# EasyEDA_proj.net
KiCad netlist of a schematic drawn in EasyEDA Pro
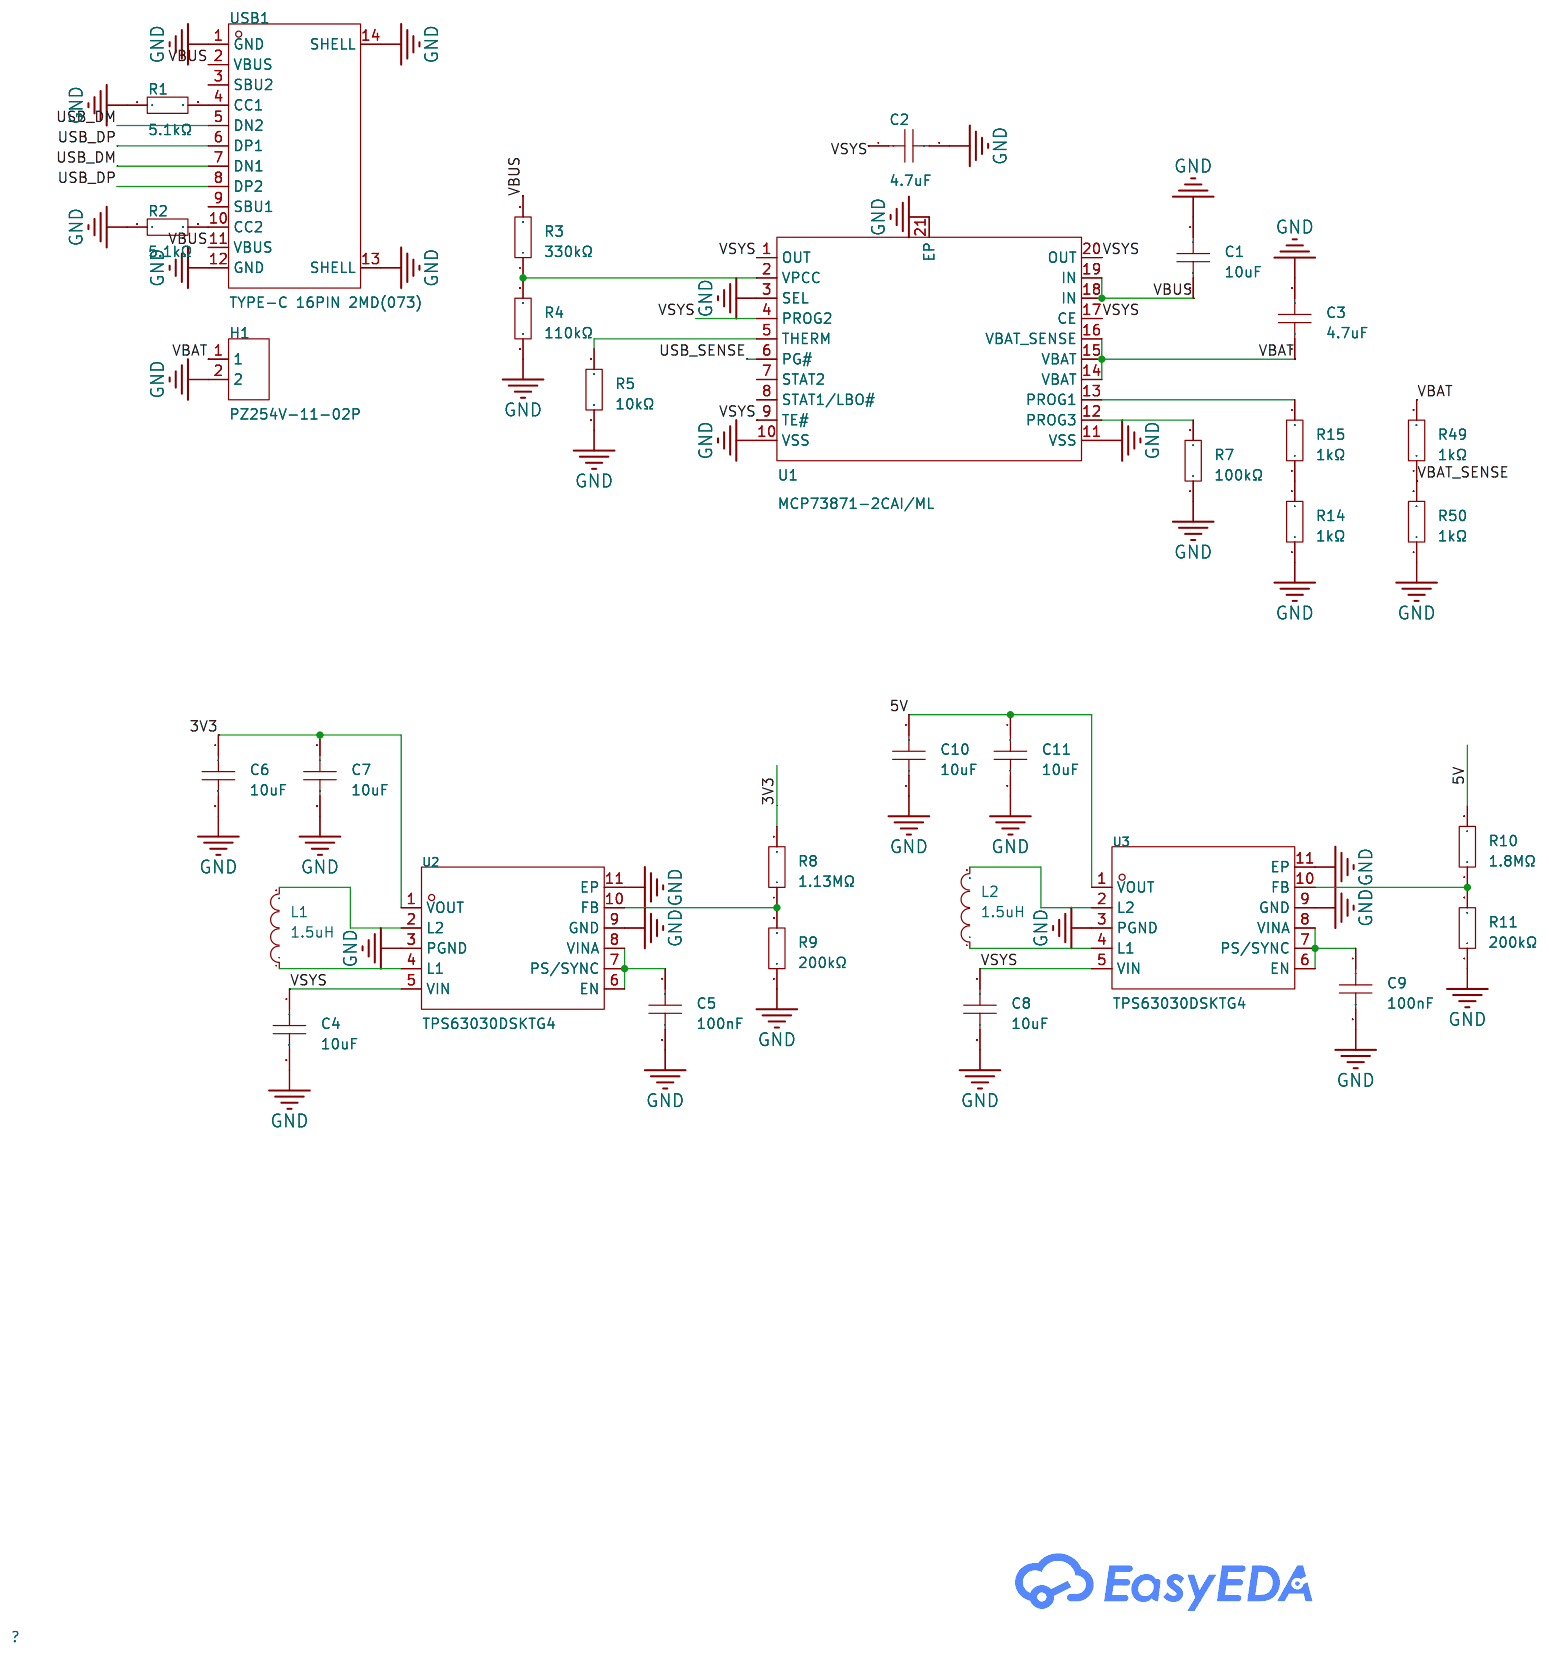
[diagram p0: Power]
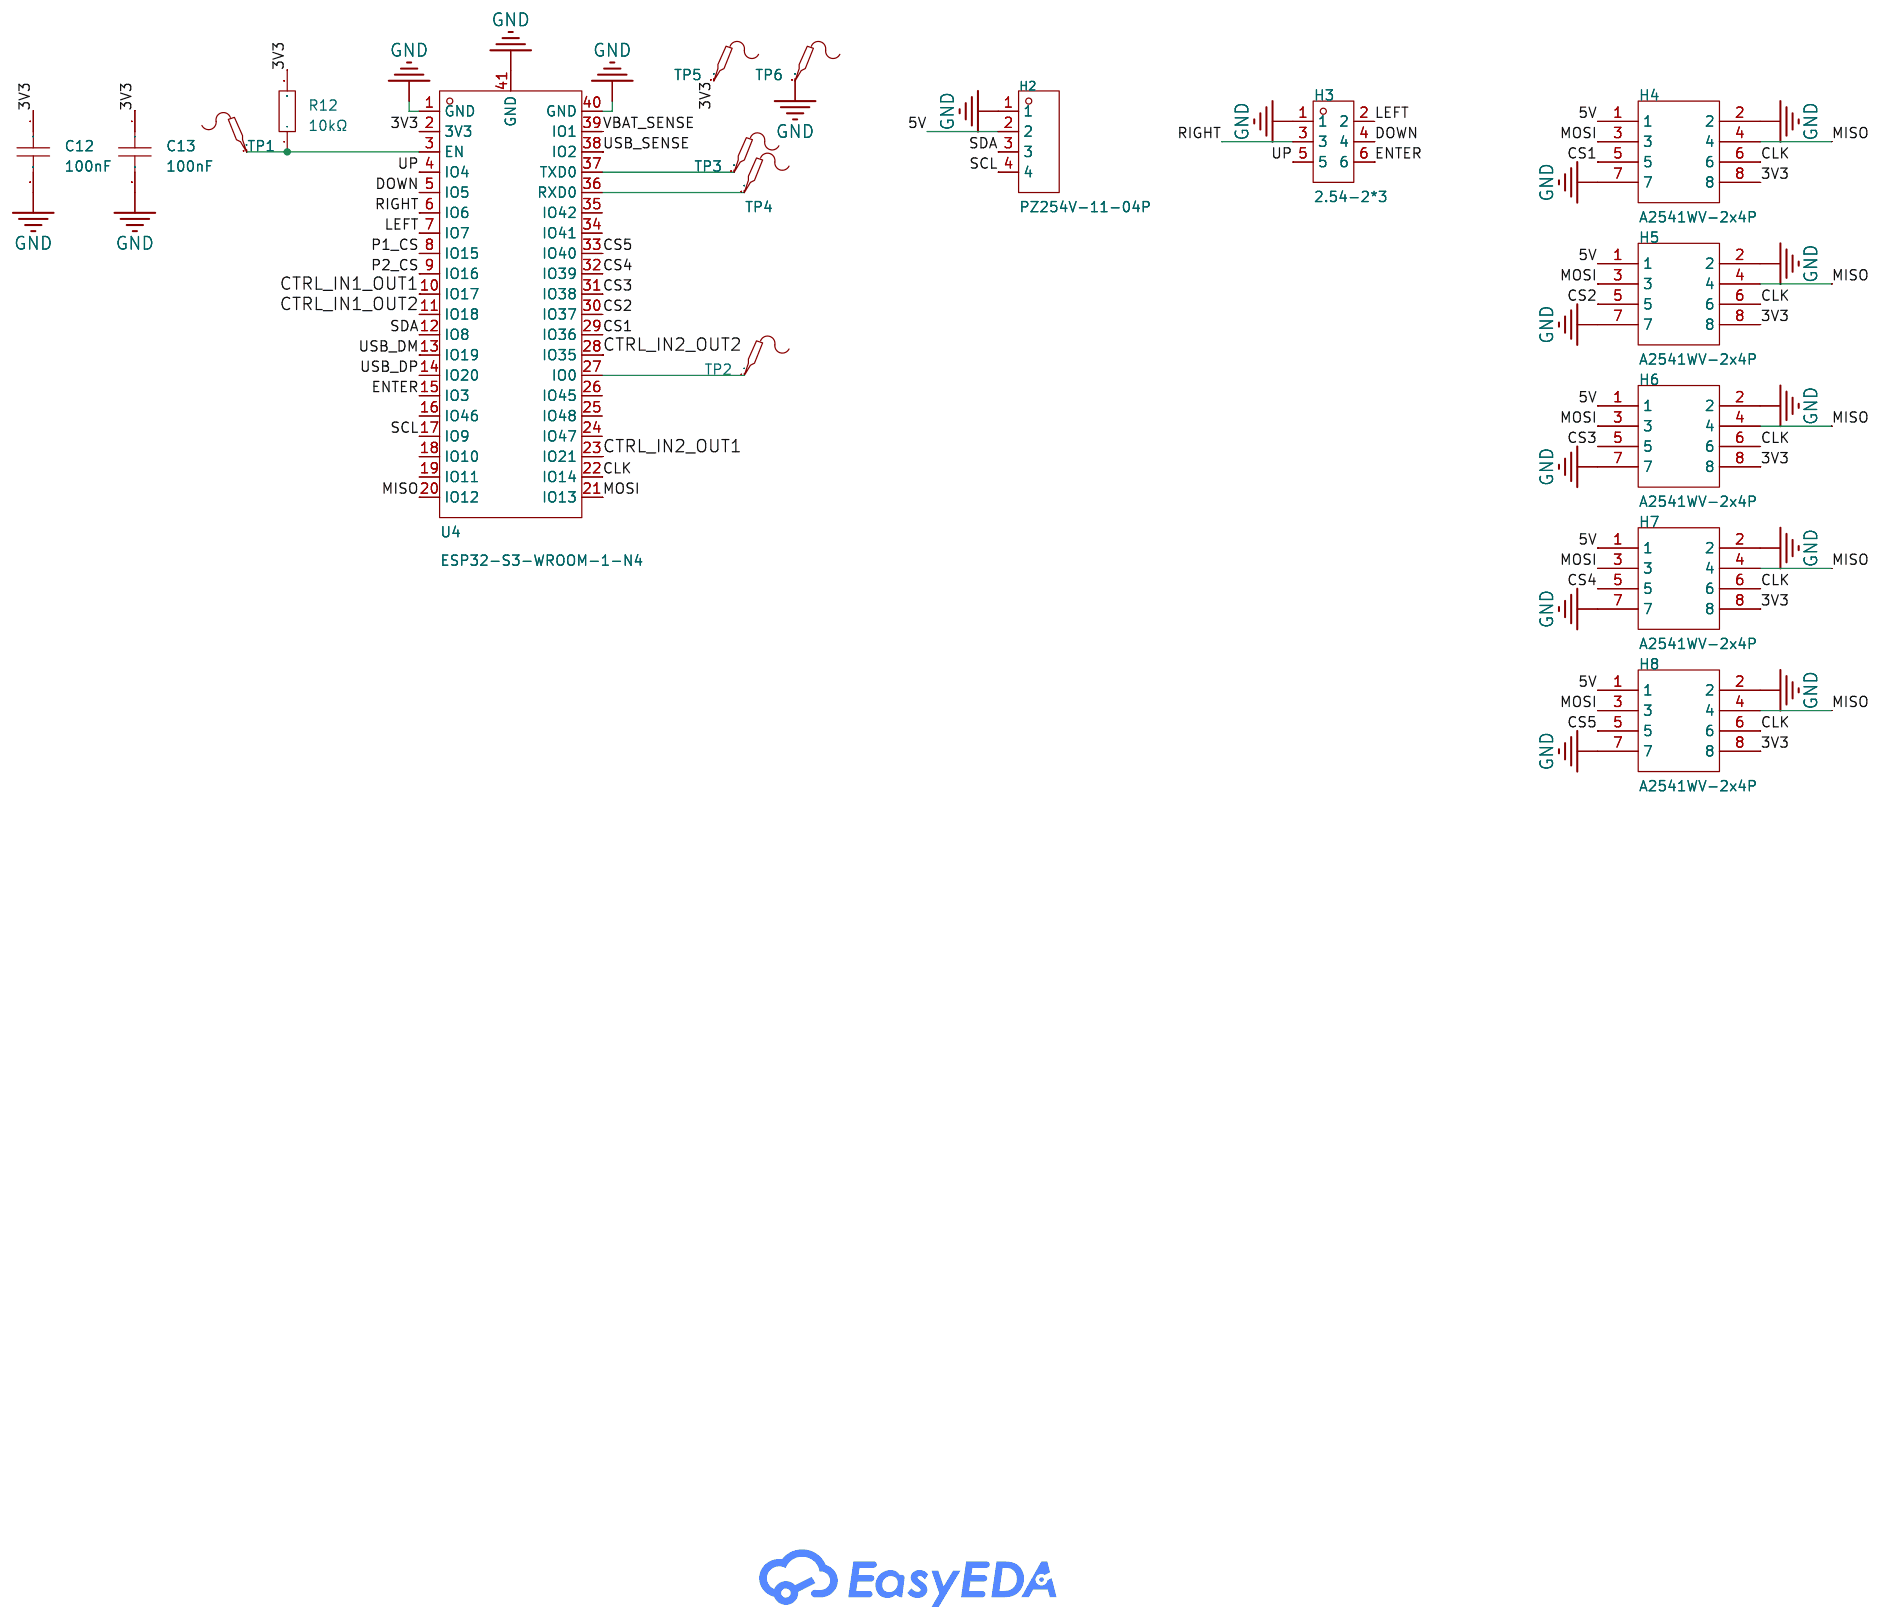
[diagram p1: MCU]
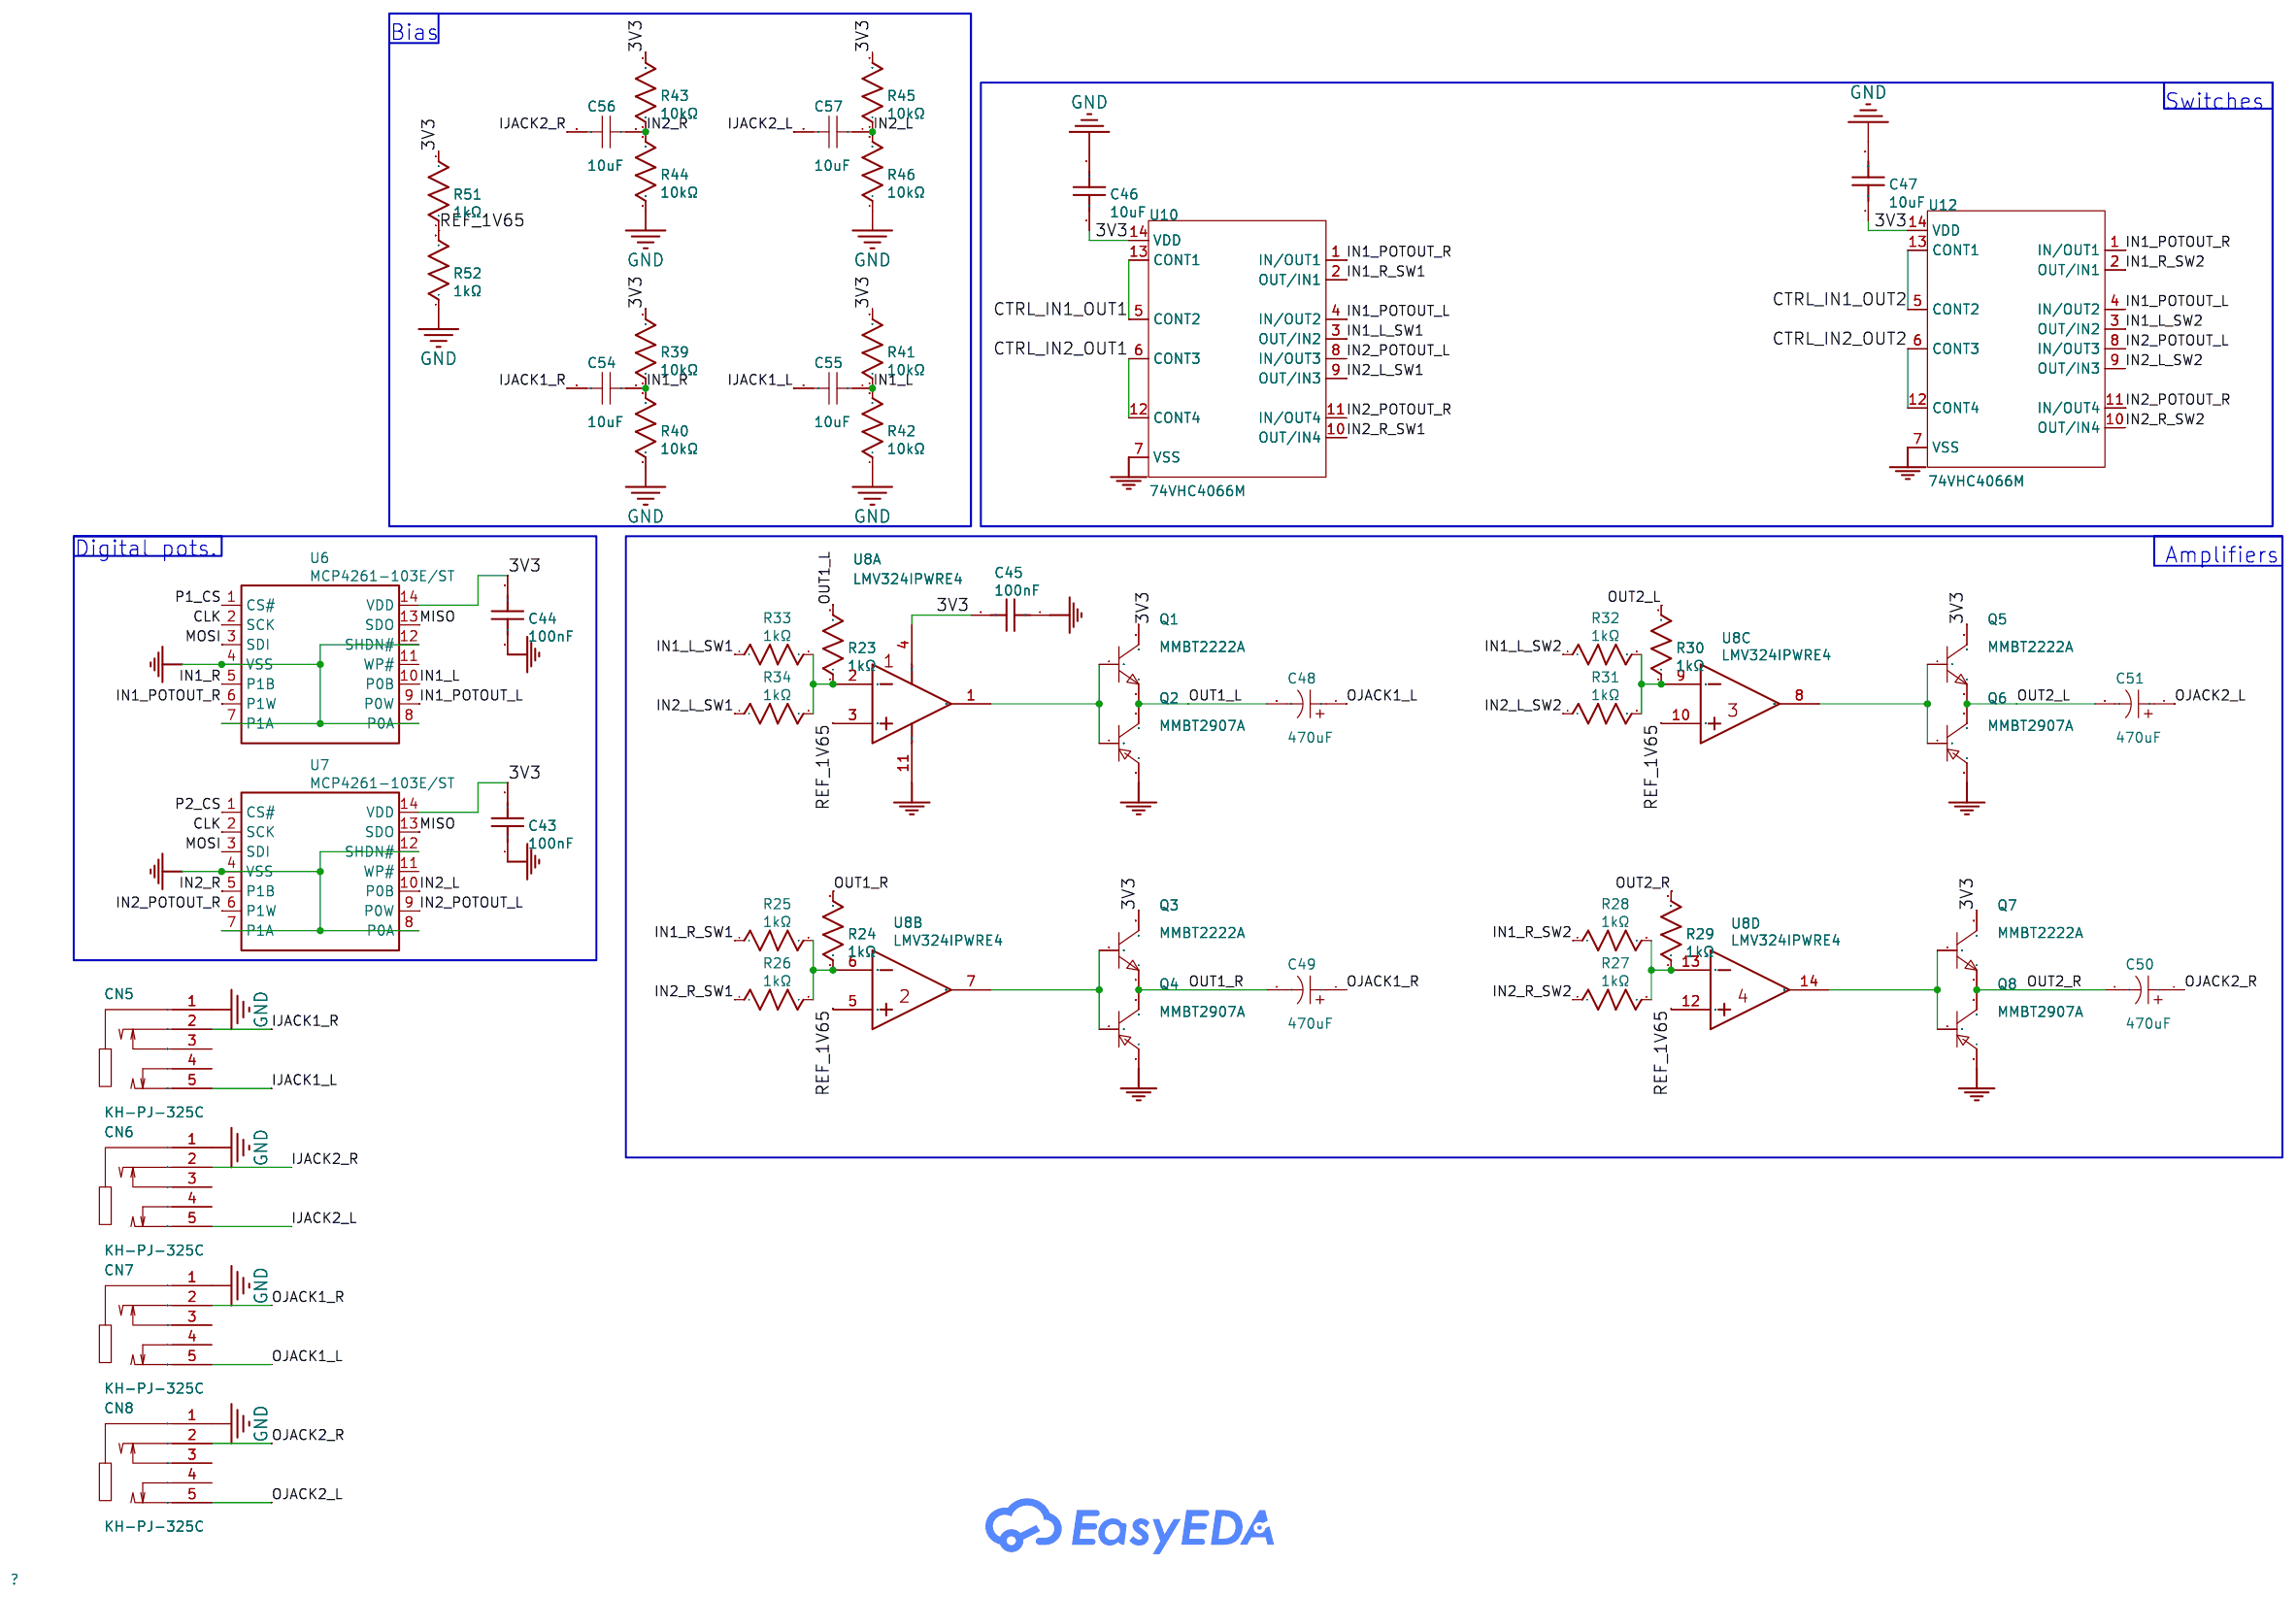
[diagram p2: Audio]

(export (version "E")
  (design (tool "Eeschema 10.0.6"))
  (components
    (comp (ref "C1")
      (value "10uF")
      (footprint "easyedapro:C0603")
      (description "Capacitance:10uF Tolerance:±20% Tolerance:±20% Voltage Rating:6.3V Temperature Coefficient:X5R")
      (fields (field (name "Manufacturer Part") "C0603B106M007T") (field (name "Manufacturer") "IHHEC(禾伸堂)"))
      (libsource (lib "easyedapro") (part "CAP"))
    )
    (comp (ref "C2")
      (value "4.7uF")
      (footprint "easyedapro:C0603")
      (description "Capacitance:4.7uF Tolerance:±10% Tolerance:±10% Voltage Rating:10V Temperature Coefficient:X5R")
      (fields
        (field (name "Manufacturer Part") "CL10A475KP8NNNC")
        (field (name "Manufacturer") "SAMSUNG(三星)")
      )
      (libsource (lib "easyedapro") (part "CAP"))
    )
    (comp (ref "C3")
      (value "4.7uF")
      (footprint "easyedapro:C0603")
      (description "Capacitance:4.7uF Tolerance:±10% Tolerance:±10% Voltage Rating:10V Temperature Coefficient:X5R")
      (fields
        (field (name "Manufacturer Part") "CL10A475KP8NNNC")
        (field (name "Manufacturer") "SAMSUNG(三星)")
      )
      (libsource (lib "easyedapro") (part "CAP"))
    )
    (comp (ref "C4")
      (value "10uF")
      (footprint "easyedapro:C0603")
      (description "Capacitance:10uF Tolerance:±20% Tolerance:±20% Voltage Rating:6.3V Temperature Coefficient:X5R")
      (fields (field (name "Manufacturer Part") "C0603B106M007T") (field (name "Manufacturer") "IHHEC(禾伸堂)"))
      (libsource (lib "easyedapro") (part "CAP"))
    )
    (comp (ref "C5")
      (value "100nF")
      (footprint "easyedapro:C0603")
      (description "Capacitance:100nF Tolerance:±10% Tolerance:±10% Voltage Rating:50V Temperature Coefficient:X7R")
      (fields
        (field (name "Manufacturer Part") "CC0603KRX7R9BB104")
        (field (name "Manufacturer") "YAGEO(国巨)")
      )
      (libsource (lib "easyedapro") (part "CAP"))
    )
    (comp (ref "C6")
      (value "10uF")
      (footprint "easyedapro:C0603")
      (description "Capacitance:10uF Tolerance:±20% Tolerance:±20% Voltage Rating:6.3V Temperature Coefficient:X5R")
      (fields (field (name "Manufacturer Part") "C0603B106M007T") (field (name "Manufacturer") "IHHEC(禾伸堂)"))
      (libsource (lib "easyedapro") (part "CAP"))
    )
    (comp (ref "C7")
      (value "10uF")
      (footprint "easyedapro:C0603")
      (description "Capacitance:10uF Tolerance:±20% Tolerance:±20% Voltage Rating:6.3V Temperature Coefficient:X5R")
      (fields (field (name "Manufacturer Part") "C0603B106M007T") (field (name "Manufacturer") "IHHEC(禾伸堂)"))
      (libsource (lib "easyedapro") (part "CAP"))
    )
    (comp (ref "C8")
      (value "10uF")
      (footprint "easyedapro:C0603")
      (description "Capacitance:10uF Tolerance:±20% Tolerance:±20% Voltage Rating:6.3V Temperature Coefficient:X5R")
      (fields (field (name "Manufacturer Part") "C0603B106M007T") (field (name "Manufacturer") "IHHEC(禾伸堂)"))
      (libsource (lib "easyedapro") (part "CAP"))
    )
    (comp (ref "C9")
      (value "100nF")
      (footprint "easyedapro:C0603")
      (description "Capacitance:100nF Tolerance:±10% Tolerance:±10% Voltage Rating:50V Temperature Coefficient:X7R")
      (fields
        (field (name "Manufacturer Part") "CC0603KRX7R9BB104")
        (field (name "Manufacturer") "YAGEO(国巨)")
      )
      (libsource (lib "easyedapro") (part "CAP"))
    )
    (comp (ref "C10")
      (value "10uF")
      (footprint "easyedapro:C0603")
      (description "Capacitance:10uF Tolerance:±20% Tolerance:±20% Voltage Rating:6.3V Temperature Coefficient:X5R")
      (fields (field (name "Manufacturer Part") "C0603B106M007T") (field (name "Manufacturer") "IHHEC(禾伸堂)"))
      (libsource (lib "easyedapro") (part "CAP"))
    )
    (comp (ref "C11")
      (value "10uF")
      (footprint "easyedapro:C0603")
      (description "Capacitance:10uF Tolerance:±20% Tolerance:±20% Voltage Rating:6.3V Temperature Coefficient:X5R")
      (fields (field (name "Manufacturer Part") "C0603B106M007T") (field (name "Manufacturer") "IHHEC(禾伸堂)"))
      (libsource (lib "easyedapro") (part "CAP"))
    )
    (comp (ref "H1")
      (value "PZ254V-11-02P")
      (footprint "easyedapro:HDR-TH_2P-P2.54-V-M")
      (fields (field (name "Manufacturer") "XFCN(兴飞)"))
      (libsource (lib "easyedapro") (part "PZ254V-11-02P"))
    )
    (comp (ref "L1")
      (value "1.5uH")
      (footprint "easyedapro:L0603")
      (fields
        (field (name "Manufacturer Part") "LB3218T1R5M")
        (field (name "Manufacturer") "TAIYO YUDEN(太诱)")
      )
      (libsource (lib "easyedapro") (part "电感"))
    )
    (comp (ref "L2")
      (value "1.5uH")
      (footprint "easyedapro:L0603")
      (fields
        (field (name "Manufacturer Part") "LB3218T1R5M")
        (field (name "Manufacturer") "TAIYO YUDEN(太诱)")
      )
      (libsource (lib "easyedapro") (part "电感"))
    )
    (comp (ref "R1")
      (value "5.1kΩ")
      (footprint "easyedapro:R0603")
      (fields
        (field (name "Manufacturer Part") "HoAR0603-1/10W-5.1KR-0.1%-TCR25")
        (field (name "Manufacturer") "Milliohm(毫欧)")
      )
      (libsource (lib "easyedapro") (part "Res"))
    )
    (comp (ref "R2")
      (value "5.1kΩ")
      (footprint "easyedapro:R0603")
      (fields
        (field (name "Manufacturer Part") "HoAR0603-1/10W-5.1KR-0.1%-TCR25")
        (field (name "Manufacturer") "Milliohm(毫欧)")
      )
      (libsource (lib "easyedapro") (part "Res"))
    )
    (comp (ref "R3")
      (value "330kΩ")
      (footprint "easyedapro:R0603")
      (fields (field (name "Manufacturer Part") "HPCR0603F330KK9") (field (name "Manufacturer") "RESI(开步睿思)"))
      (libsource (lib "easyedapro") (part "Res"))
    )
    (comp (ref "R4")
      (value "110kΩ")
      (footprint "easyedapro:R0603")
      (fields (field (name "Manufacturer Part") "PTFR0603B110KN9") (field (name "Manufacturer") "RESI(开步睿思)"))
      (libsource (lib "easyedapro") (part "Res"))
    )
    (comp (ref "R5")
      (value "10kΩ")
      (footprint "easyedapro:R0603")
      (fields (field (name "Manufacturer Part") "SCR0603J10K") (field (name "Manufacturer") "VO(翔胜)"))
      (libsource (lib "easyedapro") (part "Res"))
    )
    (comp (ref "R7")
      (value "100kΩ")
      (footprint "easyedapro:R0603")
      (fields (field (name "Manufacturer Part") "SCR0603F100K") (field (name "Manufacturer") "VO(翔胜)"))
      (libsource (lib "easyedapro") (part "Res"))
    )
    (comp (ref "R8")
      (value "1.13MΩ")
      (footprint "easyedapro:R0603")
      (fields (field (name "Manufacturer Part") "RTT031134FTP") (field (name "Manufacturer") "RALEC(旺诠)"))
      (libsource (lib "easyedapro") (part "Res"))
    )
    (comp (ref "R9")
      (value "200kΩ")
      (footprint "easyedapro:R0603")
      (fields (field (name "Manufacturer Part") "SCR0603F200K") (field (name "Manufacturer") "VO(翔胜)"))
      (libsource (lib "easyedapro") (part "Res"))
    )
    (comp (ref "R10")
      (value "1.8MΩ")
      (footprint "easyedapro:R0603")
      (fields (field (name "Manufacturer Part") "FRC0603J185TS") (field (name "Manufacturer") "FOJAN(富捷)"))
      (libsource (lib "easyedapro") (part "Res"))
    )
    (comp (ref "R11")
      (value "200kΩ")
      (footprint "easyedapro:R0603")
      (fields (field (name "Manufacturer Part") "SCR0603F200K") (field (name "Manufacturer") "VO(翔胜)"))
      (libsource (lib "easyedapro") (part "Res"))
    )
    (comp (ref "R14")
      (value "1kΩ")
      (footprint "easyedapro:R0603")
      (fields
        (field (name "Manufacturer Part") "0603WAF1001T5E")
        (field (name "Manufacturer") "UNI-ROYAL(厚声)")
      )
      (libsource (lib "easyedapro") (part "Res"))
    )
    (comp (ref "R15")
      (value "1kΩ")
      (footprint "easyedapro:R0603")
      (fields
        (field (name "Manufacturer Part") "0603WAF1001T5E")
        (field (name "Manufacturer") "UNI-ROYAL(厚声)")
      )
      (libsource (lib "easyedapro") (part "Res"))
    )
    (comp (ref "R49")
      (value "1kΩ")
      (footprint "easyedapro:R0603")
      (fields
        (field (name "Manufacturer Part") "0603WAF1001T5E")
        (field (name "Manufacturer") "UNI-ROYAL(厚声)")
      )
      (libsource (lib "easyedapro") (part "Res"))
    )
    (comp (ref "R50")
      (value "1kΩ")
      (footprint "easyedapro:R0603")
      (fields
        (field (name "Manufacturer Part") "0603WAF1001T5E")
        (field (name "Manufacturer") "UNI-ROYAL(厚声)")
      )
      (libsource (lib "easyedapro") (part "Res"))
    )
    (comp (ref "U1")
      (value "MCP73871-2CAI/ML")
      (footprint "easyedapro:QFN-20_L4.0-W4.0-P0.50-BL-EP2.7")
      (fields (field (name "Manufacturer") "MICROCHIP(美国微芯)"))
      (libsource (lib "easyedapro") (part "MCP73871-2CAI/ML"))
    )
    (comp (ref "U2")
      (value "TPS63030DSKTG4")
      (footprint "easyedapro:SON-10_L2.5-W2.5-P0.50-TL-EP")
      (fields (field (name "Manufacturer") "TI(德州仪器)"))
      (libsource (lib "easyedapro") (part "TPS63030DSKTG4"))
    )
    (comp (ref "U3")
      (value "TPS63030DSKTG4")
      (footprint "easyedapro:SON-10_L2.5-W2.5-P0.50-TL-EP")
      (fields (field (name "Manufacturer") "TI(德州仪器)"))
      (libsource (lib "easyedapro") (part "TPS63030DSKTG4"))
    )
    (comp (ref "USB1")
      (value "TYPE-C 16PIN 2MD(073)")
      (footprint "easyedapro:USB-C-SMD_TYPE-C-6PIN-2MD-073")
      (fields (field (name "Manufacturer") "SHOU HAN(首韩)"))
      (libsource (lib "easyedapro") (part "TYPE-C 16PIN 2MD(073)"))
    )
    (comp (ref "C12")
      (value "100nF")
      (footprint "easyedapro:C0603")
      (description "Capacitance:100nF Tolerance:±10% Tolerance:±10% Voltage Rating:50V Temperature Coefficient:X7R")
      (fields
        (field (name "Manufacturer Part") "CC0603KRX7R9BB104")
        (field (name "Manufacturer") "YAGEO(国巨)")
      )
      (libsource (lib "easyedapro") (part "CAP"))
    )
    (comp (ref "C13")
      (value "100nF")
      (footprint "easyedapro:C0603")
      (description "Capacitance:100nF Tolerance:±10% Tolerance:±10% Voltage Rating:50V Temperature Coefficient:X7R")
      (fields
        (field (name "Manufacturer Part") "CC0603KRX7R9BB104")
        (field (name "Manufacturer") "YAGEO(国巨)")
      )
      (libsource (lib "easyedapro") (part "CAP"))
    )
    (comp (ref "H2")
      (value "PZ254V-11-04P")
      (footprint "easyedapro:HDR-TH_4P-P2.54-V-M")
      (fields (field (name "Manufacturer") "XFCN(兴飞)"))
      (libsource (lib "easyedapro") (part "PZ254V-11-04P_C2691448"))
    )
    (comp (ref "H3")
      (value "2.54-2*3")
      (footprint "easyedapro:HDR-TH_6P-P2.54-V-R2-C3-S2.54_A2541WV-2X3P")
      (fields (field (name "Manufacturer") "ZHOURI(洲日)"))
      (libsource (lib "easyedapro") (part "2.54-2*3"))
    )
    (comp (ref "H4")
      (value "A2541WV-2x4P")
      (footprint "easyedapro:HDR-TH_8P-P2.54-V-R2-C4-S2.54_A2541WV-2X4P")
      (fields (field (name "Manufacturer") "CJT(长江连接器)"))
      (libsource (lib "easyedapro") (part "A2541WV-2X4P"))
    )
    (comp (ref "H5")
      (value "A2541WV-2x4P")
      (footprint "easyedapro:HDR-TH_8P-P2.54-V-R2-C4-S2.54_A2541WV-2X4P")
      (fields (field (name "Manufacturer") "CJT(长江连接器)"))
      (libsource (lib "easyedapro") (part "A2541WV-2X4P"))
    )
    (comp (ref "H6")
      (value "A2541WV-2x4P")
      (footprint "easyedapro:HDR-TH_8P-P2.54-V-R2-C4-S2.54_A2541WV-2X4P")
      (fields (field (name "Manufacturer") "CJT(长江连接器)"))
      (libsource (lib "easyedapro") (part "A2541WV-2X4P"))
    )
    (comp (ref "H7")
      (value "A2541WV-2x4P")
      (footprint "easyedapro:HDR-TH_8P-P2.54-V-R2-C4-S2.54_A2541WV-2X4P")
      (fields (field (name "Manufacturer") "CJT(长江连接器)"))
      (libsource (lib "easyedapro") (part "A2541WV-2X4P"))
    )
    (comp (ref "H8")
      (value "A2541WV-2x4P")
      (footprint "easyedapro:HDR-TH_8P-P2.54-V-R2-C4-S2.54_A2541WV-2X4P")
      (fields (field (name "Manufacturer") "CJT(长江连接器)"))
      (libsource (lib "easyedapro") (part "A2541WV-2X4P"))
    )
    (comp (ref "R12")
      (value "10kΩ")
      (footprint "easyedapro:R0603")
      (fields (field (name "Manufacturer Part") "SCR0603J10K") (field (name "Manufacturer") "VO(翔胜)"))
      (libsource (lib "easyedapro") (part "Res"))
    )
    (comp (ref "TP1")
      (value "~")
      (footprint "easyedapro:Test-Point-0.5mm")
      (description "Test Point 测试点")
      (libsource (lib "easyedapro") (part "Test-Point"))
    )
    (comp (ref "TP2")
      (value "~")
      (footprint "easyedapro:Test-Point-0.5mm")
      (description "Test Point 测试点")
      (libsource (lib "easyedapro") (part "Test-Point"))
    )
    (comp (ref "TP3")
      (value "~")
      (footprint "easyedapro:Test-Point-0.5mm")
      (description "Test Point 测试点")
      (libsource (lib "easyedapro") (part "Test-Point"))
    )
    (comp (ref "TP4")
      (value "~")
      (footprint "easyedapro:Test-Point-0.5mm")
      (description "Test Point 测试点")
      (libsource (lib "easyedapro") (part "Test-Point"))
    )
    (comp (ref "TP5")
      (value "~")
      (footprint "easyedapro:Test-Point-0.5mm")
      (description "Test Point 测试点")
      (libsource (lib "easyedapro") (part "Test-Point"))
    )
    (comp (ref "TP6")
      (value "~")
      (footprint "easyedapro:Test-Point-0.5mm")
      (description "Test Point 测试点")
      (libsource (lib "easyedapro") (part "Test-Point"))
    )
    (comp (ref "U4")
      (value "ESP32-S3-WROOM-1-N4")
      (footprint "easyedapro:WIFIM-SMD_ESP32-S3-WROOM-1-N8")
      (fields (field (name "Manufacturer") "ESPRESSIF(乐鑫)"))
      (libsource (lib "easyedapro") (part "ESP32-S3-WROOM-1-N4"))
    )
    (comp (ref "C43")
      (value "100nF")
      (footprint "easyedapro:C0603")
      (description "Capacitance:100nF Tolerance:±10% Tolerance:±10% Voltage Rating:50V Temperature Coefficient:X7R")
      (fields (field (name "Manufacturer") "YAGEO(国巨)"))
      (libsource (lib "easyedapro") (part "0.1u"))
    )
    (comp (ref "C44")
      (value "100nF")
      (footprint "easyedapro:C0603")
      (description "Capacitance:100nF Tolerance:±10% Tolerance:±10% Voltage Rating:50V Temperature Coefficient:X7R")
      (fields (field (name "Manufacturer") "YAGEO(国巨)"))
      (libsource (lib "easyedapro") (part "0.1u"))
    )
    (comp (ref "C45")
      (value "100nF")
      (footprint "easyedapro:C0603")
      (description "Capacitance:100nF Tolerance:±10% Tolerance:±10% Voltage Rating:50V Temperature Coefficient:X7R")
      (fields (field (name "Manufacturer") "YAGEO(国巨)"))
      (libsource (lib "easyedapro") (part "0.1u"))
    )
    (comp (ref "C46")
      (value "10uF")
      (footprint "easyedapro:C0603")
      (description "Capacitance:10uF Tolerance:±20% Tolerance:±20% Voltage Rating:6.3V Temperature Coefficient:X5R")
      (fields (field (name "Manufacturer") "IHHEC(禾伸堂)"))
      (libsource (lib "easyedapro") (part "10uF"))
    )
    (comp (ref "C47")
      (value "10uF")
      (footprint "easyedapro:C0603")
      (description "Capacitance:10uF Tolerance:±20% Tolerance:±20% Voltage Rating:6.3V Temperature Coefficient:X5R")
      (fields (field (name "Manufacturer") "IHHEC(禾伸堂)"))
      (libsource (lib "easyedapro") (part "10uF"))
    )
    (comp (ref "C48")
      (value "470uF")
      (footprint "easyedapro:CAP-SMD_L7.3-W4.3-FD")
      (fields
        (field (name "Manufacturer Part") "CA45-D-6.3V-470UF-K")
        (field (name "Manufacturer") "CEC(振华新云)")
      )
      (libsource (lib "easyedapro") (part "CA45-D-6.3V-470UF-K"))
    )
    (comp (ref "C49")
      (value "470uF")
      (footprint "easyedapro:CAP-SMD_L7.3-W4.3-FD")
      (fields
        (field (name "Manufacturer Part") "CA45-D-6.3V-470UF-K")
        (field (name "Manufacturer") "CEC(振华新云)")
      )
      (libsource (lib "easyedapro") (part "CA45-D-6.3V-470UF-K"))
    )
    (comp (ref "C50")
      (value "470uF")
      (footprint "easyedapro:CAP-SMD_L7.3-W4.3-FD")
      (fields
        (field (name "Manufacturer Part") "CA45-D-6.3V-470UF-K")
        (field (name "Manufacturer") "CEC(振华新云)")
      )
      (libsource (lib "easyedapro") (part "CA45-D-6.3V-470UF-K"))
    )
    (comp (ref "C51")
      (value "470uF")
      (footprint "easyedapro:CAP-SMD_L7.3-W4.3-FD")
      (fields
        (field (name "Manufacturer Part") "CA45-D-6.3V-470UF-K")
        (field (name "Manufacturer") "CEC(振华新云)")
      )
      (libsource (lib "easyedapro") (part "CA45-D-6.3V-470UF-K"))
    )
    (comp (ref "C54")
      (value "10uF")
      (footprint "easyedapro:C0603")
      (description "Capacitance:10uF Tolerance:±20% Tolerance:±20% Voltage Rating:6.3V Temperature Coefficient:X5R")
      (fields (field (name "Manufacturer Part") "C0603B106M007T") (field (name "Manufacturer") "IHHEC(禾伸堂)"))
      (libsource (lib "easyedapro") (part "CAP"))
    )
    (comp (ref "C55")
      (value "10uF")
      (footprint "easyedapro:C0603")
      (description "Capacitance:10uF Tolerance:±20% Tolerance:±20% Voltage Rating:6.3V Temperature Coefficient:X5R")
      (fields (field (name "Manufacturer Part") "C0603B106M007T") (field (name "Manufacturer") "IHHEC(禾伸堂)"))
      (libsource (lib "easyedapro") (part "CAP"))
    )
    (comp (ref "C56")
      (value "10uF")
      (footprint "easyedapro:C0603")
      (description "Capacitance:10uF Tolerance:±20% Tolerance:±20% Voltage Rating:6.3V Temperature Coefficient:X5R")
      (fields (field (name "Manufacturer Part") "C0603B106M007T") (field (name "Manufacturer") "IHHEC(禾伸堂)"))
      (libsource (lib "easyedapro") (part "CAP"))
    )
    (comp (ref "C57")
      (value "10uF")
      (footprint "easyedapro:C0603")
      (description "Capacitance:10uF Tolerance:±20% Tolerance:±20% Voltage Rating:6.3V Temperature Coefficient:X5R")
      (fields (field (name "Manufacturer Part") "C0603B106M007T") (field (name "Manufacturer") "IHHEC(禾伸堂)"))
      (libsource (lib "easyedapro") (part "CAP"))
    )
    (comp (ref "CN5")
      (value "KH-PJ-325C")
      (footprint "easyedapro:AUDIO-TH_KH-PJ-325C")
      (description "Connector Type:3.5mm Headphone Jack Contact Material:Brass；Bronze Contact Plating:Gold；Tin")
      (fields (field (name "Manufacturer") "kinghelm(金航标)"))
      (libsource (lib "easyedapro") (part "KH-PJ-325C"))
    )
    (comp (ref "CN6")
      (value "KH-PJ-325C")
      (footprint "easyedapro:AUDIO-TH_KH-PJ-325C")
      (description "Connector Type:3.5mm Headphone Jack Contact Material:Brass；Bronze Contact Plating:Gold；Tin")
      (fields (field (name "Manufacturer") "kinghelm(金航标)"))
      (libsource (lib "easyedapro") (part "KH-PJ-325C"))
    )
    (comp (ref "CN7")
      (value "KH-PJ-325C")
      (footprint "easyedapro:AUDIO-TH_KH-PJ-325C")
      (description "Connector Type:3.5mm Headphone Jack Contact Material:Brass；Bronze Contact Plating:Gold；Tin")
      (fields (field (name "Manufacturer") "kinghelm(金航标)"))
      (libsource (lib "easyedapro") (part "KH-PJ-325C"))
    )
    (comp (ref "CN8")
      (value "KH-PJ-325C")
      (footprint "easyedapro:AUDIO-TH_KH-PJ-325C")
      (description "Connector Type:3.5mm Headphone Jack Contact Material:Brass；Bronze Contact Plating:Gold；Tin")
      (fields (field (name "Manufacturer") "kinghelm(金航标)"))
      (libsource (lib "easyedapro") (part "KH-PJ-325C"))
    )
    (comp (ref "Q1")
      (value "MMBT2222A")
      (footprint "easyedapro:SOT-23-3_L2.9-W1.6-P1.90-LS2.8-BR")
      (fields (field (name "Manufacturer") "TDSEMIC(拓电半导体)"))
      (libsource (lib "easyedapro") (part "MMBT2222A_C42441802"))
    )
    (comp (ref "Q2")
      (value "MMBT2907A")
      (footprint "easyedapro:SOT-23-3_L2.9-W1.3-P1.90-LS2.4-BR")
      (fields (field (name "Manufacturer") "R+O(宏嘉诚)"))
      (libsource (lib "easyedapro") (part "MMBT2907A_C7420352"))
    )
    (comp (ref "Q3")
      (value "MMBT2222A")
      (footprint "easyedapro:SOT-23-3_L2.9-W1.6-P1.90-LS2.8-BR")
      (fields (field (name "Manufacturer") "TDSEMIC(拓电半导体)"))
      (libsource (lib "easyedapro") (part "MMBT2222A_C42441802"))
    )
    (comp (ref "Q4")
      (value "MMBT2907A")
      (footprint "easyedapro:SOT-23-3_L2.9-W1.3-P1.90-LS2.4-BR")
      (fields (field (name "Manufacturer") "R+O(宏嘉诚)"))
      (libsource (lib "easyedapro") (part "MMBT2907A_C7420352"))
    )
    (comp (ref "Q5")
      (value "MMBT2222A")
      (footprint "easyedapro:SOT-23-3_L2.9-W1.6-P1.90-LS2.8-BR")
      (fields (field (name "Manufacturer") "TDSEMIC(拓电半导体)"))
      (libsource (lib "easyedapro") (part "MMBT2222A_C42441802"))
    )
    (comp (ref "Q6")
      (value "MMBT2907A")
      (footprint "easyedapro:SOT-23-3_L2.9-W1.3-P1.90-LS2.4-BR")
      (fields (field (name "Manufacturer") "R+O(宏嘉诚)"))
      (libsource (lib "easyedapro") (part "MMBT2907A_C7420352"))
    )
    (comp (ref "Q7")
      (value "MMBT2222A")
      (footprint "easyedapro:SOT-23-3_L2.9-W1.6-P1.90-LS2.8-BR")
      (fields (field (name "Manufacturer") "TDSEMIC(拓电半导体)"))
      (libsource (lib "easyedapro") (part "MMBT2222A_C42441802"))
    )
    (comp (ref "Q8")
      (value "MMBT2907A")
      (footprint "easyedapro:SOT-23-3_L2.9-W1.3-P1.90-LS2.4-BR")
      (fields (field (name "Manufacturer") "R+O(宏嘉诚)"))
      (libsource (lib "easyedapro") (part "MMBT2907A_C7420352"))
    )
    (comp (ref "R23")
      (value "1kΩ")
      (footprint "easyedapro:R0603")
      (fields (field (name "Manufacturer") "UNI-ROYAL(厚声)"))
      (libsource (lib "easyedapro") (part "1k"))
    )
    (comp (ref "R24")
      (value "1kΩ")
      (footprint "easyedapro:R0603")
      (fields (field (name "Manufacturer") "UNI-ROYAL(厚声)"))
      (libsource (lib "easyedapro") (part "1k"))
    )
    (comp (ref "R25")
      (value "1kΩ")
      (footprint "easyedapro:R0603")
      (fields (field (name "Manufacturer") "UNI-ROYAL(厚声)"))
      (libsource (lib "easyedapro") (part "1k"))
    )
    (comp (ref "R26")
      (value "1kΩ")
      (footprint "easyedapro:R0603")
      (fields (field (name "Manufacturer") "UNI-ROYAL(厚声)"))
      (libsource (lib "easyedapro") (part "1k"))
    )
    (comp (ref "R27")
      (value "1kΩ")
      (footprint "easyedapro:R0603")
      (fields (field (name "Manufacturer") "UNI-ROYAL(厚声)"))
      (libsource (lib "easyedapro") (part "1k"))
    )
    (comp (ref "R28")
      (value "1kΩ")
      (footprint "easyedapro:R0603")
      (fields (field (name "Manufacturer") "UNI-ROYAL(厚声)"))
      (libsource (lib "easyedapro") (part "1k"))
    )
    (comp (ref "R29")
      (value "1kΩ")
      (footprint "easyedapro:R0603")
      (fields (field (name "Manufacturer") "UNI-ROYAL(厚声)"))
      (libsource (lib "easyedapro") (part "1k"))
    )
    (comp (ref "R30")
      (value "1kΩ")
      (footprint "easyedapro:R0603")
      (fields (field (name "Manufacturer") "UNI-ROYAL(厚声)"))
      (libsource (lib "easyedapro") (part "1k"))
    )
    (comp (ref "R31")
      (value "1kΩ")
      (footprint "easyedapro:R0603")
      (fields (field (name "Manufacturer") "UNI-ROYAL(厚声)"))
      (libsource (lib "easyedapro") (part "1k"))
    )
    (comp (ref "R32")
      (value "1kΩ")
      (footprint "easyedapro:R0603")
      (fields (field (name "Manufacturer") "UNI-ROYAL(厚声)"))
      (libsource (lib "easyedapro") (part "1k"))
    )
    (comp (ref "R33")
      (value "1kΩ")
      (footprint "easyedapro:R0603")
      (fields (field (name "Manufacturer") "UNI-ROYAL(厚声)"))
      (libsource (lib "easyedapro") (part "1k"))
    )
    (comp (ref "R34")
      (value "1kΩ")
      (footprint "easyedapro:R0603")
      (fields (field (name "Manufacturer") "UNI-ROYAL(厚声)"))
      (libsource (lib "easyedapro") (part "1k"))
    )
    (comp (ref "R39")
      (value "10kΩ")
      (footprint "easyedapro:R0603")
      (fields (field (name "Manufacturer") "VO(翔胜)"))
      (libsource (lib "easyedapro") (part "1k"))
    )
    (comp (ref "R40")
      (value "10kΩ")
      (footprint "easyedapro:R0603")
      (fields (field (name "Manufacturer") "VO(翔胜)"))
      (libsource (lib "easyedapro") (part "1k"))
    )
    (comp (ref "R41")
      (value "10kΩ")
      (footprint "easyedapro:R0603")
      (fields (field (name "Manufacturer") "VO(翔胜)"))
      (libsource (lib "easyedapro") (part "1k"))
    )
    (comp (ref "R42")
      (value "10kΩ")
      (footprint "easyedapro:R0603")
      (fields (field (name "Manufacturer") "VO(翔胜)"))
      (libsource (lib "easyedapro") (part "1k"))
    )
    (comp (ref "R43")
      (value "10kΩ")
      (footprint "easyedapro:R0603")
      (fields (field (name "Manufacturer") "VO(翔胜)"))
      (libsource (lib "easyedapro") (part "1k"))
    )
    (comp (ref "R44")
      (value "10kΩ")
      (footprint "easyedapro:R0603")
      (fields (field (name "Manufacturer") "VO(翔胜)"))
      (libsource (lib "easyedapro") (part "1k"))
    )
    (comp (ref "R45")
      (value "10kΩ")
      (footprint "easyedapro:R0603")
      (fields (field (name "Manufacturer") "VO(翔胜)"))
      (libsource (lib "easyedapro") (part "1k"))
    )
    (comp (ref "R46")
      (value "10kΩ")
      (footprint "easyedapro:R0603")
      (fields (field (name "Manufacturer") "VO(翔胜)"))
      (libsource (lib "easyedapro") (part "1k"))
    )
    (comp (ref "R51")
      (value "1kΩ")
      (footprint "easyedapro:R0603")
      (fields (field (name "Manufacturer") "UNI-ROYAL(厚声)"))
      (libsource (lib "easyedapro") (part "1k"))
    )
    (comp (ref "R52")
      (value "1kΩ")
      (footprint "easyedapro:R0603")
      (fields (field (name "Manufacturer") "UNI-ROYAL(厚声)"))
      (libsource (lib "easyedapro") (part "1k"))
    )
    (comp (ref "U6")
      (value "MCP4261-103E/ST")
      (footprint "easyedapro:TSSOP-14_L5.0-W4.4-P0.65-LS6.4-BL")
      (fields (field (name "Manufacturer") "MICROCHIP(美国微芯)") (field (name "Contributor") "LCSC"))
      (libsource (lib "easyedapro") (part "MCP4261-103E/ST"))
    )
    (comp (ref "U7")
      (value "MCP4261-103E/ST")
      (footprint "easyedapro:TSSOP-14_L5.0-W4.4-P0.65-LS6.4-BL")
      (fields (field (name "Manufacturer") "MICROCHIP(美国微芯)") (field (name "Contributor") "LCSC"))
      (libsource (lib "easyedapro") (part "MCP4261-103E/ST"))
    )
    (comp (ref "U8")
      (value "LMV324IPWRE4")
      (footprint "easyedapro:TSSOP-14_L5.0-W4.4-P0.65-LS6.4-BL")
      (fields (field (name "Manufacturer") "TI(德州仪器)") (field (name "subpart_no") "1"))
      (libsource (lib "easyedapro") (part "LMV324IPWRE4"))
    )
    (comp (ref "U10")
      (value "74VHC4066M")
      (footprint "easyedapro:PDIP-14_L19.7-W6.6-P2.54-LS8.3-BL")
      (fields (field (name "Manufacturer") "onsemi(安森美)"))
      (libsource (lib "easyedapro") (part "74VHC4066N"))
    )
    (comp (ref "U12")
      (value "74VHC4066M")
      (footprint "easyedapro:PDIP-14_L19.7-W6.6-P2.54-LS8.3-BL")
      (fields (field (name "Manufacturer") "onsemi(安森美)"))
      (libsource (lib "easyedapro") (part "74VHC4066N"))
    )
  )
  (nets
    (net (code "1") (name "3V3") (class "Default")
      (node (ref "C12") (pin "1") (pinfunction "1_1") (pintype "input"))
      (node (ref "C13") (pin "1") (pinfunction "1_1") (pintype "input"))
      (node (ref "C43") (pin "2") (pinfunction "2_2") (pintype "unspecified"))
      (node (ref "C44") (pin "2") (pinfunction "2_2") (pintype "unspecified"))
      (node (ref "C45") (pin "2") (pinfunction "2_2") (pintype "unspecified"))
      (node (ref "C46") (pin "1") (pinfunction "1_1") (pintype "unspecified"))
      (node (ref "C47") (pin "1") (pinfunction "1_1") (pintype "unspecified"))
      (node (ref "C6") (pin "1") (pinfunction "1_1") (pintype "input"))
      (node (ref "C7") (pin "1") (pinfunction "1_1") (pintype "input"))
      (node (ref "H4") (pin "8") (pinfunction "8_8") (pintype "unspecified"))
      (node (ref "H5") (pin "8") (pinfunction "8_8") (pintype "unspecified"))
      (node (ref "H6") (pin "8") (pinfunction "8_8") (pintype "unspecified"))
      (node (ref "H7") (pin "8") (pinfunction "8_8") (pintype "unspecified"))
      (node (ref "H8") (pin "8") (pinfunction "8_8") (pintype "unspecified"))
      (node (ref "Q1") (pin "3") (pinfunction "C_3") (pintype "input"))
      (node (ref "Q3") (pin "3") (pinfunction "C_3") (pintype "input"))
      (node (ref "Q5") (pin "3") (pinfunction "C_3") (pintype "input"))
      (node (ref "Q7") (pin "3") (pinfunction "C_3") (pintype "input"))
      (node (ref "R12") (pin "2") (pinfunction "2_2") (pintype "input"))
      (node (ref "R39") (pin "2") (pinfunction "2_2") (pintype "unspecified"))
      (node (ref "R41") (pin "2") (pinfunction "2_2") (pintype "unspecified"))
      (node (ref "R43") (pin "2") (pinfunction "2_2") (pintype "unspecified"))
      (node (ref "R45") (pin "2") (pinfunction "2_2") (pintype "unspecified"))
      (node (ref "R51") (pin "2") (pinfunction "2_2") (pintype "unspecified"))
      (node (ref "R8") (pin "2") (pinfunction "2_2") (pintype "input"))
      (node (ref "TP5") (pin "1") (pinfunction "1_1") (pintype "unspecified"))
      (node (ref "U10") (pin "14") (pinfunction "VDD_14") (pintype "unspecified"))
      (node (ref "U12") (pin "14") (pinfunction "VDD_14") (pintype "unspecified"))
      (node (ref "U2") (pin "1") (pinfunction "VOUT_1") (pintype "input"))
      (node (ref "U4") (pin "2") (pinfunction "3V3_2") (pintype "unspecified"))
      (node (ref "U6") (pin "14") (pinfunction "VDD_14") (pintype "unspecified"))
      (node (ref "U7") (pin "14") (pinfunction "VDD_14") (pintype "unspecified"))
      (node (ref "U8") (pin "4") (pinfunction "VCC+_4") (pintype "unspecified"))
    )
    (net (code "2") (name "5V") (class "Default")
      (node (ref "C10") (pin "1") (pinfunction "1_1") (pintype "input"))
      (node (ref "C11") (pin "1") (pinfunction "1_1") (pintype "input"))
      (node (ref "H2") (pin "2") (pinfunction "2_2") (pintype "input"))
      (node (ref "H4") (pin "1") (pinfunction "1_1") (pintype "unspecified"))
      (node (ref "H5") (pin "1") (pinfunction "1_1") (pintype "unspecified"))
      (node (ref "H6") (pin "1") (pinfunction "1_1") (pintype "unspecified"))
      (node (ref "H7") (pin "1") (pinfunction "1_1") (pintype "unspecified"))
      (node (ref "H8") (pin "1") (pinfunction "1_1") (pintype "unspecified"))
      (node (ref "R10") (pin "2") (pinfunction "2_2") (pintype "input"))
      (node (ref "U3") (pin "1") (pinfunction "VOUT_1") (pintype "input"))
    )
    (net (code "3") (name "CLK") (class "Default")
      (node (ref "H4") (pin "6") (pinfunction "6_6") (pintype "unspecified"))
      (node (ref "H5") (pin "6") (pinfunction "6_6") (pintype "unspecified"))
      (node (ref "H6") (pin "6") (pinfunction "6_6") (pintype "unspecified"))
      (node (ref "H7") (pin "6") (pinfunction "6_6") (pintype "unspecified"))
      (node (ref "H8") (pin "6") (pinfunction "6_6") (pintype "unspecified"))
      (node (ref "U4") (pin "22") (pinfunction "IO14_22") (pintype "unspecified"))
      (node (ref "U6") (pin "2") (pinfunction "SCK_2") (pintype "unspecified"))
      (node (ref "U7") (pin "2") (pinfunction "SCK_2") (pintype "unspecified"))
    )
    (net (code "4") (name "CS1") (class "Default")
      (node (ref "H4") (pin "5") (pinfunction "5_5") (pintype "unspecified"))
      (node (ref "U4") (pin "29") (pinfunction "IO36_29") (pintype "unspecified"))
    )
    (net (code "5") (name "CS2") (class "Default")
      (node (ref "H5") (pin "5") (pinfunction "5_5") (pintype "unspecified"))
      (node (ref "U4") (pin "30") (pinfunction "IO37_30") (pintype "unspecified"))
    )
    (net (code "6") (name "CS3") (class "Default")
      (node (ref "H6") (pin "5") (pinfunction "5_5") (pintype "unspecified"))
      (node (ref "U4") (pin "31") (pinfunction "IO38_31") (pintype "unspecified"))
    )
    (net (code "7") (name "CS4") (class "Default")
      (node (ref "H7") (pin "5") (pinfunction "5_5") (pintype "unspecified"))
      (node (ref "U4") (pin "32") (pinfunction "IO39_32") (pintype "unspecified"))
    )
    (net (code "8") (name "CS5") (class "Default")
      (node (ref "H8") (pin "5") (pinfunction "5_5") (pintype "unspecified"))
      (node (ref "U4") (pin "33") (pinfunction "IO40_33") (pintype "unspecified"))
    )
    (net (code "9") (name "CTRL_IN1_OUT1") (class "Default")
      (node (ref "U10") (pin "13") (pinfunction "CONT1_13") (pintype "unspecified"))
      (node (ref "U10") (pin "5") (pinfunction "CONT2_5") (pintype "unspecified"))
      (node (ref "U4") (pin "10") (pinfunction "IO17_10") (pintype "unspecified"))
    )
    (net (code "10") (name "CTRL_IN1_OUT2") (class "Default")
      (node (ref "U12") (pin "13") (pinfunction "CONT1_13") (pintype "unspecified"))
      (node (ref "U12") (pin "5") (pinfunction "CONT2_5") (pintype "unspecified"))
      (node (ref "U4") (pin "11") (pinfunction "IO18_11") (pintype "unspecified"))
    )
    (net (code "11") (name "CTRL_IN2_OUT1") (class "Default")
      (node (ref "U10") (pin "12") (pinfunction "CONT4_12") (pintype "unspecified"))
      (node (ref "U10") (pin "6") (pinfunction "CONT3_6") (pintype "unspecified"))
      (node (ref "U4") (pin "23") (pinfunction "IO21_23") (pintype "unspecified"))
    )
    (net (code "12") (name "CTRL_IN2_OUT2") (class "Default")
      (node (ref "U12") (pin "12") (pinfunction "CONT4_12") (pintype "unspecified"))
      (node (ref "U12") (pin "6") (pinfunction "CONT3_6") (pintype "unspecified"))
      (node (ref "U4") (pin "28") (pinfunction "IO35_28") (pintype "unspecified"))
    )
    (net (code "13") (name "DOWN") (class "Default")
      (node (ref "H3") (pin "4") (pinfunction "4_4") (pintype "unspecified"))
      (node (ref "U4") (pin "5") (pinfunction "IO5_5") (pintype "unspecified"))
    )
    (net (code "14") (name "ENTER") (class "Default")
      (node (ref "H3") (pin "6") (pinfunction "6_6") (pintype "unspecified"))
      (node (ref "U4") (pin "15") (pinfunction "IO3_15") (pintype "unspecified"))
    )
    (net (code "15") (name "GND") (class "Default")
      (node (ref "C1") (pin "1") (pinfunction "1_1") (pintype "input"))
      (node (ref "C10") (pin "2") (pinfunction "2_2") (pintype "input"))
      (node (ref "C11") (pin "2") (pinfunction "2_2") (pintype "input"))
      (node (ref "C12") (pin "2") (pinfunction "2_2") (pintype "input"))
      (node (ref "C13") (pin "2") (pinfunction "2_2") (pintype "input"))
      (node (ref "C2") (pin "2") (pinfunction "2_2") (pintype "input"))
      (node (ref "C3") (pin "2") (pinfunction "2_2") (pintype "input"))
      (node (ref "C4") (pin "2") (pinfunction "2_2") (pintype "input"))
      (node (ref "C43") (pin "1") (pinfunction "1_1") (pintype "unspecified"))
      (node (ref "C44") (pin "1") (pinfunction "1_1") (pintype "unspecified"))
      (node (ref "C45") (pin "1") (pinfunction "1_1") (pintype "unspecified"))
      (node (ref "C46") (pin "2") (pinfunction "2_2") (pintype "unspecified"))
      (node (ref "C47") (pin "2") (pinfunction "2_2") (pintype "unspecified"))
      (node (ref "C5") (pin "2") (pinfunction "2_2") (pintype "input"))
      (node (ref "C6") (pin "2") (pinfunction "2_2") (pintype "input"))
      (node (ref "C7") (pin "2") (pinfunction "2_2") (pintype "input"))
      (node (ref "C8") (pin "2") (pinfunction "2_2") (pintype "input"))
      (node (ref "C9") (pin "2") (pinfunction "2_2") (pintype "input"))
      (node (ref "CN5") (pin "1") (pinfunction "1_1") (pintype "unspecified"))
      (node (ref "CN6") (pin "1") (pinfunction "1_1") (pintype "unspecified"))
      (node (ref "CN7") (pin "1") (pinfunction "1_1") (pintype "unspecified"))
      (node (ref "CN8") (pin "1") (pinfunction "1_1") (pintype "unspecified"))
      (node (ref "H1") (pin "2") (pinfunction "2_2") (pintype "unspecified"))
      (node (ref "H2") (pin "1") (pinfunction "1_1") (pintype "input"))
      (node (ref "H3") (pin "1") (pinfunction "1_1") (pintype "unspecified"))
      (node (ref "H4") (pin "2") (pinfunction "2_2") (pintype "unspecified"))
      (node (ref "H4") (pin "7") (pinfunction "7_7") (pintype "unspecified"))
      (node (ref "H5") (pin "2") (pinfunction "2_2") (pintype "unspecified"))
      (node (ref "H5") (pin "7") (pinfunction "7_7") (pintype "unspecified"))
      (node (ref "H6") (pin "2") (pinfunction "2_2") (pintype "unspecified"))
      (node (ref "H6") (pin "7") (pinfunction "7_7") (pintype "unspecified"))
      (node (ref "H7") (pin "2") (pinfunction "2_2") (pintype "unspecified"))
      (node (ref "H7") (pin "7") (pinfunction "7_7") (pintype "unspecified"))
      (node (ref "H8") (pin "2") (pinfunction "2_2") (pintype "unspecified"))
      (node (ref "H8") (pin "7") (pinfunction "7_7") (pintype "unspecified"))
      (node (ref "Q2") (pin "2") (pinfunction "E_2") (pintype "unspecified"))
      (node (ref "Q4") (pin "2") (pinfunction "E_2") (pintype "unspecified"))
      (node (ref "Q6") (pin "2") (pinfunction "E_2") (pintype "unspecified"))
      (node (ref "Q8") (pin "2") (pinfunction "E_2") (pintype "unspecified"))
      (node (ref "R1") (pin "1") (pinfunction "1_1") (pintype "input"))
      (node (ref "R11") (pin "1") (pinfunction "1_1") (pintype "input"))
      (node (ref "R14") (pin "1") (pinfunction "1_1") (pintype "input"))
      (node (ref "R2") (pin "1") (pinfunction "1_1") (pintype "input"))
      (node (ref "R4") (pin "1") (pinfunction "1_1") (pintype "input"))
      (node (ref "R40") (pin "1") (pinfunction "1_1") (pintype "unspecified"))
      (node (ref "R42") (pin "1") (pinfunction "1_1") (pintype "unspecified"))
      (node (ref "R44") (pin "1") (pinfunction "1_1") (pintype "unspecified"))
      (node (ref "R46") (pin "1") (pinfunction "1_1") (pintype "unspecified"))
      (node (ref "R5") (pin "1") (pinfunction "1_1") (pintype "input"))
      (node (ref "R50") (pin "1") (pinfunction "1_1") (pintype "input"))
      (node (ref "R52") (pin "1") (pinfunction "1_1") (pintype "unspecified"))
      (node (ref "R7") (pin "1") (pinfunction "1_1") (pintype "input"))
      (node (ref "R9") (pin "1") (pinfunction "1_1") (pintype "input"))
      (node (ref "TP6") (pin "1") (pinfunction "1_1") (pintype "unspecified"))
      (node (ref "U1") (pin "10") (pinfunction "VSS_10") (pintype "unspecified"))
      (node (ref "U1") (pin "11") (pinfunction "VSS_11") (pintype "unspecified"))
      (node (ref "U1") (pin "21") (pinfunction "EP_21") (pintype "unspecified"))
      (node (ref "U1") (pin "3") (pinfunction "SEL_3") (pintype "unspecified"))
      (node (ref "U10") (pin "7") (pinfunction "VSS_7") (pintype "unspecified"))
      (node (ref "U12") (pin "7") (pinfunction "VSS_7") (pintype "unspecified"))
      (node (ref "U2") (pin "11") (pinfunction "EP_11") (pintype "input"))
      (node (ref "U2") (pin "3") (pinfunction "PGND_3") (pintype "input"))
      (node (ref "U2") (pin "9") (pinfunction "GND_9") (pintype "input"))
      (node (ref "U3") (pin "11") (pinfunction "EP_11") (pintype "input"))
      (node (ref "U3") (pin "3") (pinfunction "PGND_3") (pintype "input"))
      (node (ref "U3") (pin "9") (pinfunction "GND_9") (pintype "input"))
      (node (ref "U4") (pin "1") (pinfunction "GND_1") (pintype "unspecified"))
      (node (ref "U4") (pin "40") (pinfunction "GND_40") (pintype "unspecified"))
      (node (ref "U4") (pin "41") (pinfunction "GND_41") (pintype "unspecified"))
      (node (ref "U6") (pin "12") (pinfunction "SHDN#_12") (pintype "unspecified"))
      (node (ref "U6") (pin "4") (pinfunction "VSS_4") (pintype "unspecified"))
      (node (ref "U6") (pin "7") (pinfunction "P1A_7") (pintype "unspecified"))
      (node (ref "U6") (pin "8") (pinfunction "P0A_8") (pintype "unspecified"))
      (node (ref "U7") (pin "12") (pinfunction "SHDN#_12") (pintype "unspecified"))
      (node (ref "U7") (pin "4") (pinfunction "VSS_4") (pintype "unspecified"))
      (node (ref "U7") (pin "7") (pinfunction "P1A_7") (pintype "unspecified"))
      (node (ref "U7") (pin "8") (pinfunction "P0A_8") (pintype "unspecified"))
      (node (ref "U8") (pin "11") (pinfunction "GND_11") (pintype "unspecified"))
      (node (ref "USB1") (pin "1") (pinfunction "GND_1") (pintype "unspecified"))
      (node (ref "USB1") (pin "12") (pinfunction "GND_12") (pintype "unspecified"))
      (node (ref "USB1") (pin "13") (pinfunction "SHELL_13") (pintype "unspecified"))
      (node (ref "USB1") (pin "14") (pinfunction "SHELL_14") (pintype "unspecified"))
    )
    (net (code "16") (name "IJACK1_L") (class "Default")
      (node (ref "C55") (pin "2") (pinfunction "2_2") (pintype "input"))
      (node (ref "CN5") (pin "5") (pinfunction "5_5") (pintype "unspecified"))
    )
    (net (code "17") (name "IJACK1_R") (class "Default")
      (node (ref "C54") (pin "2") (pinfunction "2_2") (pintype "input"))
      (node (ref "CN5") (pin "2") (pinfunction "2_2") (pintype "unspecified"))
    )
    (net (code "18") (name "IJACK2_L") (class "Default")
      (node (ref "C57") (pin "2") (pinfunction "2_2") (pintype "input"))
      (node (ref "CN6") (pin "5") (pinfunction "5_5") (pintype "unspecified"))
    )
    (net (code "19") (name "IJACK2_R") (class "Default")
      (node (ref "C56") (pin "2") (pinfunction "2_2") (pintype "input"))
      (node (ref "CN6") (pin "2") (pinfunction "2_2") (pintype "unspecified"))
    )
    (net (code "20") (name "IN1_L") (class "Default")
      (node (ref "C55") (pin "1") (pinfunction "1_1") (pintype "input"))
      (node (ref "R41") (pin "1") (pinfunction "1_1") (pintype "unspecified"))
      (node (ref "R42") (pin "2") (pinfunction "2_2") (pintype "unspecified"))
      (node (ref "U6") (pin "10") (pinfunction "P0B_10") (pintype "unspecified"))
    )
    (net (code "21") (name "IN1_L_SW1") (class "Default")
      (node (ref "R33") (pin "1") (pinfunction "1_1") (pintype "unspecified"))
      (node (ref "U10") (pin "3") (pinfunction "OUT/IN2_3") (pintype "unspecified"))
    )
    (net (code "22") (name "IN1_L_SW2") (class "Default")
      (node (ref "R32") (pin "1") (pinfunction "1_1") (pintype "unspecified"))
      (node (ref "U12") (pin "3") (pinfunction "OUT/IN2_3") (pintype "unspecified"))
    )
    (net (code "23") (name "IN1_POTOUT_L") (class "Default")
      (node (ref "U10") (pin "4") (pinfunction "IN/OUT2_4") (pintype "unspecified"))
      (node (ref "U12") (pin "4") (pinfunction "IN/OUT2_4") (pintype "unspecified"))
      (node (ref "U6") (pin "9") (pinfunction "P0W_9") (pintype "unspecified"))
    )
    (net (code "24") (name "IN1_POTOUT_R") (class "Default")
      (node (ref "U10") (pin "1") (pinfunction "IN/OUT1_1") (pintype "unspecified"))
      (node (ref "U12") (pin "1") (pinfunction "IN/OUT1_1") (pintype "unspecified"))
      (node (ref "U6") (pin "6") (pinfunction "P1W_6") (pintype "unspecified"))
    )
    (net (code "25") (name "IN1_R") (class "Default")
      (node (ref "C54") (pin "1") (pinfunction "1_1") (pintype "input"))
      (node (ref "R39") (pin "1") (pinfunction "1_1") (pintype "unspecified"))
      (node (ref "R40") (pin "2") (pinfunction "2_2") (pintype "unspecified"))
      (node (ref "U6") (pin "5") (pinfunction "P1B_5") (pintype "unspecified"))
    )
    (net (code "26") (name "IN1_R_SW1") (class "Default")
      (node (ref "R25") (pin "1") (pinfunction "1_1") (pintype "unspecified"))
      (node (ref "U10") (pin "2") (pinfunction "OUT/IN1_2") (pintype "unspecified"))
    )
    (net (code "27") (name "IN1_R_SW2") (class "Default")
      (node (ref "R28") (pin "1") (pinfunction "1_1") (pintype "unspecified"))
      (node (ref "U12") (pin "2") (pinfunction "OUT/IN1_2") (pintype "unspecified"))
    )
    (net (code "28") (name "IN2_L") (class "Default")
      (node (ref "C57") (pin "1") (pinfunction "1_1") (pintype "input"))
      (node (ref "R45") (pin "1") (pinfunction "1_1") (pintype "unspecified"))
      (node (ref "R46") (pin "2") (pinfunction "2_2") (pintype "unspecified"))
      (node (ref "U7") (pin "10") (pinfunction "P0B_10") (pintype "unspecified"))
    )
    (net (code "29") (name "IN2_L_SW1") (class "Default")
      (node (ref "R34") (pin "1") (pinfunction "1_1") (pintype "unspecified"))
      (node (ref "U10") (pin "9") (pinfunction "OUT/IN3_9") (pintype "unspecified"))
    )
    (net (code "30") (name "IN2_L_SW2") (class "Default")
      (node (ref "R31") (pin "1") (pinfunction "1_1") (pintype "unspecified"))
      (node (ref "U12") (pin "9") (pinfunction "OUT/IN3_9") (pintype "unspecified"))
    )
    (net (code "31") (name "IN2_POTOUT_L") (class "Default")
      (node (ref "U10") (pin "8") (pinfunction "IN/OUT3_8") (pintype "unspecified"))
      (node (ref "U12") (pin "8") (pinfunction "IN/OUT3_8") (pintype "unspecified"))
      (node (ref "U7") (pin "9") (pinfunction "P0W_9") (pintype "unspecified"))
    )
    (net (code "32") (name "IN2_POTOUT_R") (class "Default")
      (node (ref "U10") (pin "11") (pinfunction "IN/OUT4_11") (pintype "unspecified"))
      (node (ref "U12") (pin "11") (pinfunction "IN/OUT4_11") (pintype "unspecified"))
      (node (ref "U7") (pin "6") (pinfunction "P1W_6") (pintype "unspecified"))
    )
    (net (code "33") (name "IN2_R") (class "Default")
      (node (ref "C56") (pin "1") (pinfunction "1_1") (pintype "input"))
      (node (ref "R43") (pin "1") (pinfunction "1_1") (pintype "unspecified"))
      (node (ref "R44") (pin "2") (pinfunction "2_2") (pintype "unspecified"))
      (node (ref "U7") (pin "5") (pinfunction "P1B_5") (pintype "unspecified"))
    )
    (net (code "34") (name "IN2_R_SW1") (class "Default")
      (node (ref "R26") (pin "1") (pinfunction "1_1") (pintype "unspecified"))
      (node (ref "U10") (pin "10") (pinfunction "OUT/IN4_10") (pintype "unspecified"))
    )
    (net (code "35") (name "IN2_R_SW2") (class "Default")
      (node (ref "R27") (pin "1") (pinfunction "1_1") (pintype "unspecified"))
      (node (ref "U12") (pin "10") (pinfunction "OUT/IN4_10") (pintype "unspecified"))
    )
    (net (code "36") (name "LEFT") (class "Default")
      (node (ref "H3") (pin "2") (pinfunction "2_2") (pintype "unspecified"))
      (node (ref "U4") (pin "7") (pinfunction "IO7_7") (pintype "unspecified"))
    )
    (net (code "37") (name "MISO") (class "Default")
      (node (ref "H4") (pin "4") (pinfunction "4_4") (pintype "unspecified"))
      (node (ref "H5") (pin "4") (pinfunction "4_4") (pintype "unspecified"))
      (node (ref "H6") (pin "4") (pinfunction "4_4") (pintype "unspecified"))
      (node (ref "H7") (pin "4") (pinfunction "4_4") (pintype "unspecified"))
      (node (ref "H8") (pin "4") (pinfunction "4_4") (pintype "unspecified"))
      (node (ref "U4") (pin "20") (pinfunction "IO12_20") (pintype "unspecified"))
      (node (ref "U6") (pin "13") (pinfunction "SDO_13") (pintype "unspecified"))
      (node (ref "U7") (pin "13") (pinfunction "SDO_13") (pintype "unspecified"))
    )
    (net (code "38") (name "MOSI") (class "Default")
      (node (ref "H4") (pin "3") (pinfunction "3_3") (pintype "unspecified"))
      (node (ref "H5") (pin "3") (pinfunction "3_3") (pintype "unspecified"))
      (node (ref "H6") (pin "3") (pinfunction "3_3") (pintype "unspecified"))
      (node (ref "H7") (pin "3") (pinfunction "3_3") (pintype "unspecified"))
      (node (ref "H8") (pin "3") (pinfunction "3_3") (pintype "unspecified"))
      (node (ref "U4") (pin "21") (pinfunction "IO13_21") (pintype "unspecified"))
      (node (ref "U6") (pin "3") (pinfunction "SDI_3") (pintype "unspecified"))
      (node (ref "U7") (pin "3") (pinfunction "SDI_3") (pintype "unspecified"))
    )
    (net (code "39") (name "Net-(Q1-B)") (class "Default")
      (node (ref "Q1") (pin "1") (pinfunction "B_1") (pintype "input"))
      (node (ref "Q2") (pin "1") (pinfunction "B_1") (pintype "unspecified"))
      (node (ref "U8") (pin "1") (pinfunction "OUT_1") (pintype "output"))
    )
    (net (code "40") (name "Net-(Q3-B)") (class "Default")
      (node (ref "Q3") (pin "1") (pinfunction "B_1") (pintype "input"))
      (node (ref "Q4") (pin "1") (pinfunction "B_1") (pintype "unspecified"))
      (node (ref "U8") (pin "7") (pinfunction "2OUT_7") (pintype "output"))
    )
    (net (code "41") (name "Net-(Q5-B)") (class "Default")
      (node (ref "Q5") (pin "1") (pinfunction "B_1") (pintype "input"))
      (node (ref "Q6") (pin "1") (pinfunction "B_1") (pintype "unspecified"))
      (node (ref "U8") (pin "8") (pinfunction "3OUT_8") (pintype "output"))
    )
    (net (code "42") (name "Net-(Q7-B)") (class "Default")
      (node (ref "Q7") (pin "1") (pinfunction "B_1") (pintype "input"))
      (node (ref "Q8") (pin "1") (pinfunction "B_1") (pintype "unspecified"))
      (node (ref "U8") (pin "14") (pinfunction "4OUT_14") (pintype "output"))
    )
    (net (code "43") (name "Net-(R14-Pad2)") (class "Default")
      (node (ref "R14") (pin "2") (pinfunction "2_2") (pintype "input"))
      (node (ref "R15") (pin "1") (pinfunction "1_1") (pintype "input"))
    )
    (net (code "44") (name "Net-(U1-PROG1)") (class "Default")
      (node (ref "R15") (pin "2") (pinfunction "2_2") (pintype "input"))
      (node (ref "U1") (pin "13") (pinfunction "PROG1_13") (pintype "unspecified"))
    )
    (net (code "45") (name "Net-(U1-PROG3)") (class "Default")
      (node (ref "R7") (pin "2") (pinfunction "2_2") (pintype "input"))
      (node (ref "U1") (pin "12") (pinfunction "PROG3_12") (pintype "unspecified"))
    )
    (net (code "46") (name "Net-(U1-THERM)") (class "Default")
      (node (ref "R5") (pin "2") (pinfunction "2_2") (pintype "input"))
      (node (ref "U1") (pin "5") (pinfunction "THERM_5") (pintype "unspecified"))
    )
    (net (code "47") (name "Net-(U1-VPCC)") (class "Default")
      (node (ref "R3") (pin "1") (pinfunction "1_1") (pintype "input"))
      (node (ref "R4") (pin "2") (pinfunction "2_2") (pintype "input"))
      (node (ref "U1") (pin "2") (pinfunction "VPCC_2") (pintype "unspecified"))
    )
    (net (code "48") (name "Net-(U2-EN)") (class "Default")
      (node (ref "C5") (pin "1") (pinfunction "1_1") (pintype "input"))
      (node (ref "U2") (pin "6") (pinfunction "EN_6") (pintype "input"))
      (node (ref "U2") (pin "7") (pinfunction "PS/SYNC_7") (pintype "input"))
      (node (ref "U2") (pin "8") (pinfunction "VINA_8") (pintype "input"))
    )
    (net (code "49") (name "Net-(U2-FB)") (class "Default")
      (node (ref "R8") (pin "1") (pinfunction "1_1") (pintype "input"))
      (node (ref "R9") (pin "2") (pinfunction "2_2") (pintype "input"))
      (node (ref "U2") (pin "10") (pinfunction "FB_10") (pintype "input"))
    )
    (net (code "50") (name "Net-(U2-L1)") (class "Default")
      (node (ref "L1") (pin "1") (pinfunction "1_1") (pintype "input"))
      (node (ref "U2") (pin "4") (pinfunction "L1_4") (pintype "input"))
    )
    (net (code "51") (name "Net-(U2-L2)") (class "Default")
      (node (ref "L1") (pin "2") (pinfunction "2_2") (pintype "input"))
      (node (ref "U2") (pin "2") (pinfunction "L2_2") (pintype "input"))
    )
    (net (code "52") (name "Net-(U3-EN)") (class "Default")
      (node (ref "C9") (pin "1") (pinfunction "1_1") (pintype "input"))
      (node (ref "U3") (pin "6") (pinfunction "EN_6") (pintype "input"))
      (node (ref "U3") (pin "7") (pinfunction "PS/SYNC_7") (pintype "input"))
      (node (ref "U3") (pin "8") (pinfunction "VINA_8") (pintype "input"))
    )
    (net (code "53") (name "Net-(U3-FB)") (class "Default")
      (node (ref "R10") (pin "1") (pinfunction "1_1") (pintype "input"))
      (node (ref "R11") (pin "2") (pinfunction "2_2") (pintype "input"))
      (node (ref "U3") (pin "10") (pinfunction "FB_10") (pintype "input"))
    )
    (net (code "54") (name "Net-(U3-L1)") (class "Default")
      (node (ref "L2") (pin "1") (pinfunction "1_1") (pintype "input"))
      (node (ref "U3") (pin "4") (pinfunction "L1_4") (pintype "input"))
    )
    (net (code "55") (name "Net-(U3-L2)") (class "Default")
      (node (ref "L2") (pin "2") (pinfunction "2_2") (pintype "input"))
      (node (ref "U3") (pin "2") (pinfunction "L2_2") (pintype "input"))
    )
    (net (code "56") (name "Net-(U4-EN)") (class "Default")
      (node (ref "R12") (pin "1") (pinfunction "1_1") (pintype "input"))
      (node (ref "TP1") (pin "1") (pinfunction "1_1") (pintype "unspecified"))
      (node (ref "U4") (pin "3") (pinfunction "EN_3") (pintype "unspecified"))
    )
    (net (code "57") (name "Net-(U4-IO0)") (class "Default")
      (node (ref "TP2") (pin "1") (pinfunction "1_1") (pintype "unspecified"))
      (node (ref "U4") (pin "27") (pinfunction "IO0_27") (pintype "unspecified"))
    )
    (net (code "58") (name "Net-(U4-RXD0)") (class "Default")
      (node (ref "TP4") (pin "1") (pinfunction "1_1") (pintype "unspecified"))
      (node (ref "U4") (pin "36") (pinfunction "RXD0_36") (pintype "unspecified"))
    )
    (net (code "59") (name "Net-(U4-TXD0)") (class "Default")
      (node (ref "TP3") (pin "1") (pinfunction "1_1") (pintype "unspecified"))
      (node (ref "U4") (pin "37") (pinfunction "TXD0_37") (pintype "unspecified"))
    )
    (net (code "60") (name "Net-(U8A-1IN-)") (class "Default")
      (node (ref "R23") (pin "1") (pinfunction "1_1") (pintype "unspecified"))
      (node (ref "R33") (pin "2") (pinfunction "2_2") (pintype "unspecified"))
      (node (ref "R34") (pin "2") (pinfunction "2_2") (pintype "unspecified"))
      (node (ref "U8") (pin "2") (pinfunction "1IN-_2") (pintype "unspecified"))
    )
    (net (code "61") (name "Net-(U8B-2IN-)") (class "Default")
      (node (ref "R24") (pin "1") (pinfunction "1_1") (pintype "unspecified"))
      (node (ref "R25") (pin "2") (pinfunction "2_2") (pintype "unspecified"))
      (node (ref "R26") (pin "2") (pinfunction "2_2") (pintype "unspecified"))
      (node (ref "U8") (pin "6") (pinfunction "2IN-_6") (pintype "unspecified"))
    )
    (net (code "62") (name "Net-(U8C-3IN-)") (class "Default")
      (node (ref "R30") (pin "1") (pinfunction "1_1") (pintype "unspecified"))
      (node (ref "R31") (pin "2") (pinfunction "2_2") (pintype "unspecified"))
      (node (ref "R32") (pin "2") (pinfunction "2_2") (pintype "unspecified"))
      (node (ref "U8") (pin "9") (pinfunction "3IN-_9") (pintype "unspecified"))
    )
    (net (code "63") (name "Net-(U8D-4IN-)") (class "Default")
      (node (ref "R27") (pin "2") (pinfunction "2_2") (pintype "unspecified"))
      (node (ref "R28") (pin "2") (pinfunction "2_2") (pintype "unspecified"))
      (node (ref "R29") (pin "1") (pinfunction "1_1") (pintype "unspecified"))
      (node (ref "U8") (pin "13") (pinfunction "4IN-_13") (pintype "unspecified"))
    )
    (net (code "64") (name "Net-(USB1-CC1)") (class "Default")
      (node (ref "R1") (pin "2") (pinfunction "2_2") (pintype "input"))
      (node (ref "USB1") (pin "4") (pinfunction "CC1_4") (pintype "unspecified"))
    )
    (net (code "65") (name "Net-(USB1-CC2)") (class "Default")
      (node (ref "R2") (pin "2") (pinfunction "2_2") (pintype "input"))
      (node (ref "USB1") (pin "10") (pinfunction "CC2_10") (pintype "unspecified"))
    )
    (net (code "66") (name "OJACK1_L") (class "Default")
      (node (ref "C48") (pin "1") (pinfunction "1_1") (pintype "input"))
      (node (ref "CN7") (pin "5") (pinfunction "5_5") (pintype "unspecified"))
    )
    (net (code "67") (name "OJACK1_R") (class "Default")
      (node (ref "C49") (pin "1") (pinfunction "1_1") (pintype "input"))
      (node (ref "CN7") (pin "2") (pinfunction "2_2") (pintype "unspecified"))
    )
    (net (code "68") (name "OJACK2_L") (class "Default")
      (node (ref "C51") (pin "1") (pinfunction "1_1") (pintype "input"))
      (node (ref "CN8") (pin "5") (pinfunction "5_5") (pintype "unspecified"))
    )
    (net (code "69") (name "OJACK2_R") (class "Default")
      (node (ref "C50") (pin "1") (pinfunction "1_1") (pintype "input"))
      (node (ref "CN8") (pin "2") (pinfunction "2_2") (pintype "unspecified"))
    )
    (net (code "70") (name "OUT1_L") (class "Default")
      (node (ref "C48") (pin "2") (pinfunction "2_2") (pintype "input"))
      (node (ref "Q1") (pin "2") (pinfunction "E_2") (pintype "input"))
      (node (ref "Q2") (pin "3") (pinfunction "C_3") (pintype "unspecified"))
      (node (ref "R23") (pin "2") (pinfunction "2_2") (pintype "unspecified"))
    )
    (net (code "71") (name "OUT1_R") (class "Default")
      (node (ref "C49") (pin "2") (pinfunction "2_2") (pintype "input"))
      (node (ref "Q3") (pin "2") (pinfunction "E_2") (pintype "input"))
      (node (ref "Q4") (pin "3") (pinfunction "C_3") (pintype "unspecified"))
      (node (ref "R24") (pin "2") (pinfunction "2_2") (pintype "unspecified"))
    )
    (net (code "72") (name "OUT2_L") (class "Default")
      (node (ref "C51") (pin "2") (pinfunction "2_2") (pintype "input"))
      (node (ref "Q5") (pin "2") (pinfunction "E_2") (pintype "input"))
      (node (ref "Q6") (pin "3") (pinfunction "C_3") (pintype "unspecified"))
      (node (ref "R30") (pin "2") (pinfunction "2_2") (pintype "unspecified"))
    )
    (net (code "73") (name "OUT2_R") (class "Default")
      (node (ref "C50") (pin "2") (pinfunction "2_2") (pintype "input"))
      (node (ref "Q7") (pin "2") (pinfunction "E_2") (pintype "input"))
      (node (ref "Q8") (pin "3") (pinfunction "C_3") (pintype "unspecified"))
      (node (ref "R29") (pin "2") (pinfunction "2_2") (pintype "unspecified"))
    )
    (net (code "74") (name "P1_CS") (class "Default")
      (node (ref "U4") (pin "8") (pinfunction "IO15_8") (pintype "unspecified"))
      (node (ref "U6") (pin "1") (pinfunction "CS#_1") (pintype "unspecified"))
    )
    (net (code "75") (name "P2_CS") (class "Default")
      (node (ref "U4") (pin "9") (pinfunction "IO16_9") (pintype "unspecified"))
      (node (ref "U7") (pin "1") (pinfunction "CS#_1") (pintype "unspecified"))
    )
    (net (code "76") (name "REF_1V65") (class "Default")
      (node (ref "R51") (pin "1") (pinfunction "1_1") (pintype "unspecified"))
      (node (ref "R52") (pin "2") (pinfunction "2_2") (pintype "unspecified"))
      (node (ref "U8") (pin "10") (pinfunction "3IN+_10") (pintype "unspecified"))
      (node (ref "U8") (pin "12") (pinfunction "4IN+_12") (pintype "unspecified"))
      (node (ref "U8") (pin "3") (pinfunction "1IN+_3") (pintype "unspecified"))
      (node (ref "U8") (pin "5") (pinfunction "2IN+_5") (pintype "unspecified"))
    )
    (net (code "77") (name "RIGHT") (class "Default")
      (node (ref "H3") (pin "3") (pinfunction "3_3") (pintype "unspecified"))
      (node (ref "U4") (pin "6") (pinfunction "IO6_6") (pintype "unspecified"))
    )
    (net (code "78") (name "SCL") (class "Default")
      (node (ref "H2") (pin "4") (pinfunction "4_4") (pintype "input"))
      (node (ref "U4") (pin "17") (pinfunction "IO9_17") (pintype "unspecified"))
    )
    (net (code "79") (name "SDA") (class "Default")
      (node (ref "H2") (pin "3") (pinfunction "3_3") (pintype "input"))
      (node (ref "U4") (pin "12") (pinfunction "IO8_12") (pintype "unspecified"))
    )
    (net (code "80") (name "UP") (class "Default")
      (node (ref "H3") (pin "5") (pinfunction "5_5") (pintype "unspecified"))
      (node (ref "U4") (pin "4") (pinfunction "IO4_4") (pintype "unspecified"))
    )
    (net (code "81") (name "USB_DM") (class "Default")
      (node (ref "U4") (pin "13") (pinfunction "IO19_13") (pintype "unspecified"))
      (node (ref "USB1") (pin "5") (pinfunction "DN2_5") (pintype "unspecified"))
      (node (ref "USB1") (pin "7") (pinfunction "DN1_7") (pintype "unspecified"))
    )
    (net (code "82") (name "USB_DP") (class "Default")
      (node (ref "U4") (pin "14") (pinfunction "IO20_14") (pintype "unspecified"))
      (node (ref "USB1") (pin "6") (pinfunction "DP1_6") (pintype "unspecified"))
      (node (ref "USB1") (pin "8") (pinfunction "DP2_8") (pintype "unspecified"))
    )
    (net (code "83") (name "USB_SENSE") (class "Default")
      (node (ref "U1") (pin "6") (pinfunction "PG#_6") (pintype "unspecified"))
      (node (ref "U4") (pin "38") (pinfunction "IO2_38") (pintype "unspecified"))
    )
    (net (code "84") (name "VBAT") (class "Default")
      (node (ref "C3") (pin "1") (pinfunction "1_1") (pintype "input"))
      (node (ref "H1") (pin "1") (pinfunction "1_1") (pintype "unspecified"))
      (node (ref "R49") (pin "2") (pinfunction "2_2") (pintype "input"))
      (node (ref "U1") (pin "14") (pinfunction "VBAT_14") (pintype "unspecified"))
      (node (ref "U1") (pin "15") (pinfunction "VBAT_15") (pintype "unspecified"))
      (node (ref "U1") (pin "16") (pinfunction "VBAT_SENSE_16") (pintype "unspecified"))
    )
    (net (code "85") (name "VBAT_SENSE") (class "Default")
      (node (ref "R49") (pin "1") (pinfunction "1_1") (pintype "input"))
      (node (ref "R50") (pin "2") (pinfunction "2_2") (pintype "input"))
      (node (ref "U4") (pin "39") (pinfunction "IO1_39") (pintype "unspecified"))
    )
    (net (code "86") (name "VBUS") (class "Default")
      (node (ref "C1") (pin "2") (pinfunction "2_2") (pintype "input"))
      (node (ref "R3") (pin "2") (pinfunction "2_2") (pintype "input"))
      (node (ref "U1") (pin "18") (pinfunction "IN_18") (pintype "unspecified"))
      (node (ref "U1") (pin "19") (pinfunction "IN_19") (pintype "unspecified"))
      (node (ref "USB1") (pin "11") (pinfunction "VBUS_11") (pintype "unspecified"))
      (node (ref "USB1") (pin "2") (pinfunction "VBUS_2") (pintype "unspecified"))
    )
    (net (code "87") (name "VSYS") (class "Default")
      (node (ref "C2") (pin "1") (pinfunction "1_1") (pintype "input"))
      (node (ref "C4") (pin "1") (pinfunction "1_1") (pintype "input"))
      (node (ref "C8") (pin "1") (pinfunction "1_1") (pintype "input"))
      (node (ref "U1") (pin "1") (pinfunction "OUT_1") (pintype "unspecified"))
      (node (ref "U1") (pin "17") (pinfunction "CE_17") (pintype "unspecified"))
      (node (ref "U1") (pin "20") (pinfunction "OUT_20") (pintype "unspecified"))
      (node (ref "U1") (pin "4") (pinfunction "PROG2_4") (pintype "unspecified"))
      (node (ref "U1") (pin "9") (pinfunction "TE#_9") (pintype "unspecified"))
      (node (ref "U2") (pin "5") (pinfunction "VIN_5") (pintype "input"))
      (node (ref "U3") (pin "5") (pinfunction "VIN_5") (pintype "input"))
    )
    (net (code "88") (name "unconnected-(CN5-Pad3)") (class "Default")
      (node (ref "CN5") (pin "3") (pinfunction "3_3") (pintype "unspecified"))
    )
    (net (code "89") (name "unconnected-(CN5-Pad4)") (class "Default")
      (node (ref "CN5") (pin "4") (pinfunction "4_4") (pintype "unspecified"))
    )
    (net (code "90") (name "unconnected-(CN6-Pad3)") (class "Default")
      (node (ref "CN6") (pin "3") (pinfunction "3_3") (pintype "unspecified"))
    )
    (net (code "91") (name "unconnected-(CN6-Pad4)") (class "Default")
      (node (ref "CN6") (pin "4") (pinfunction "4_4") (pintype "unspecified"))
    )
    (net (code "92") (name "unconnected-(CN7-Pad3)") (class "Default")
      (node (ref "CN7") (pin "3") (pinfunction "3_3") (pintype "unspecified"))
    )
    (net (code "93") (name "unconnected-(CN7-Pad4)") (class "Default")
      (node (ref "CN7") (pin "4") (pinfunction "4_4") (pintype "unspecified"))
    )
    (net (code "94") (name "unconnected-(CN8-Pad3)") (class "Default")
      (node (ref "CN8") (pin "3") (pinfunction "3_3") (pintype "unspecified"))
    )
    (net (code "95") (name "unconnected-(CN8-Pad4)") (class "Default")
      (node (ref "CN8") (pin "4") (pinfunction "4_4") (pintype "unspecified"))
    )
    (net (code "96") (name "unconnected-(U1-STAT1{slash}LBO#-Pad8)") (class "Default")
      (node (ref "U1") (pin "8") (pinfunction "STAT1/LBO#_8") (pintype "unspecified"))
    )
    (net (code "97") (name "unconnected-(U1-STAT2-Pad7)") (class "Default")
      (node (ref "U1") (pin "7") (pinfunction "STAT2_7") (pintype "unspecified"))
    )
    (net (code "98") (name "unconnected-(U4-IO10-Pad18)") (class "Default")
      (node (ref "U4") (pin "18") (pinfunction "IO10_18") (pintype "unspecified"))
    )
    (net (code "99") (name "unconnected-(U4-IO11-Pad19)") (class "Default")
      (node (ref "U4") (pin "19") (pinfunction "IO11_19") (pintype "unspecified"))
    )
    (net (code "100") (name "unconnected-(U4-IO41-Pad34)") (class "Default")
      (node (ref "U4") (pin "34") (pinfunction "IO41_34") (pintype "unspecified"))
    )
    (net (code "101") (name "unconnected-(U4-IO42-Pad35)") (class "Default")
      (node (ref "U4") (pin "35") (pinfunction "IO42_35") (pintype "unspecified"))
    )
    (net (code "102") (name "unconnected-(U4-IO45-Pad26)") (class "Default")
      (node (ref "U4") (pin "26") (pinfunction "IO45_26") (pintype "unspecified"))
    )
    (net (code "103") (name "unconnected-(U4-IO46-Pad16)") (class "Default")
      (node (ref "U4") (pin "16") (pinfunction "IO46_16") (pintype "unspecified"))
    )
    (net (code "104") (name "unconnected-(U4-IO47-Pad24)") (class "Default")
      (node (ref "U4") (pin "24") (pinfunction "IO47_24") (pintype "unspecified"))
    )
    (net (code "105") (name "unconnected-(U4-IO48-Pad25)") (class "Default")
      (node (ref "U4") (pin "25") (pinfunction "IO48_25") (pintype "unspecified"))
    )
    (net (code "106") (name "unconnected-(U6-WP#-Pad11)") (class "Default")
      (node (ref "U6") (pin "11") (pinfunction "WP#_11") (pintype "unspecified"))
    )
    (net (code "107") (name "unconnected-(U7-WP#-Pad11)") (class "Default")
      (node (ref "U7") (pin "11") (pinfunction "WP#_11") (pintype "unspecified"))
    )
    (net (code "108") (name "unconnected-(USB1-SBU1-Pad9)") (class "Default")
      (node (ref "USB1") (pin "9") (pinfunction "SBU1_9") (pintype "unspecified"))
    )
    (net (code "109") (name "unconnected-(USB1-SBU2-Pad3)") (class "Default")
      (node (ref "USB1") (pin "3") (pinfunction "SBU2_3") (pintype "unspecified"))
    )
  )
)
